# Lane_Detection_using_Sobel_Filter_Schema.net
KiCad netlist of a schematic drawn in Altium Designer
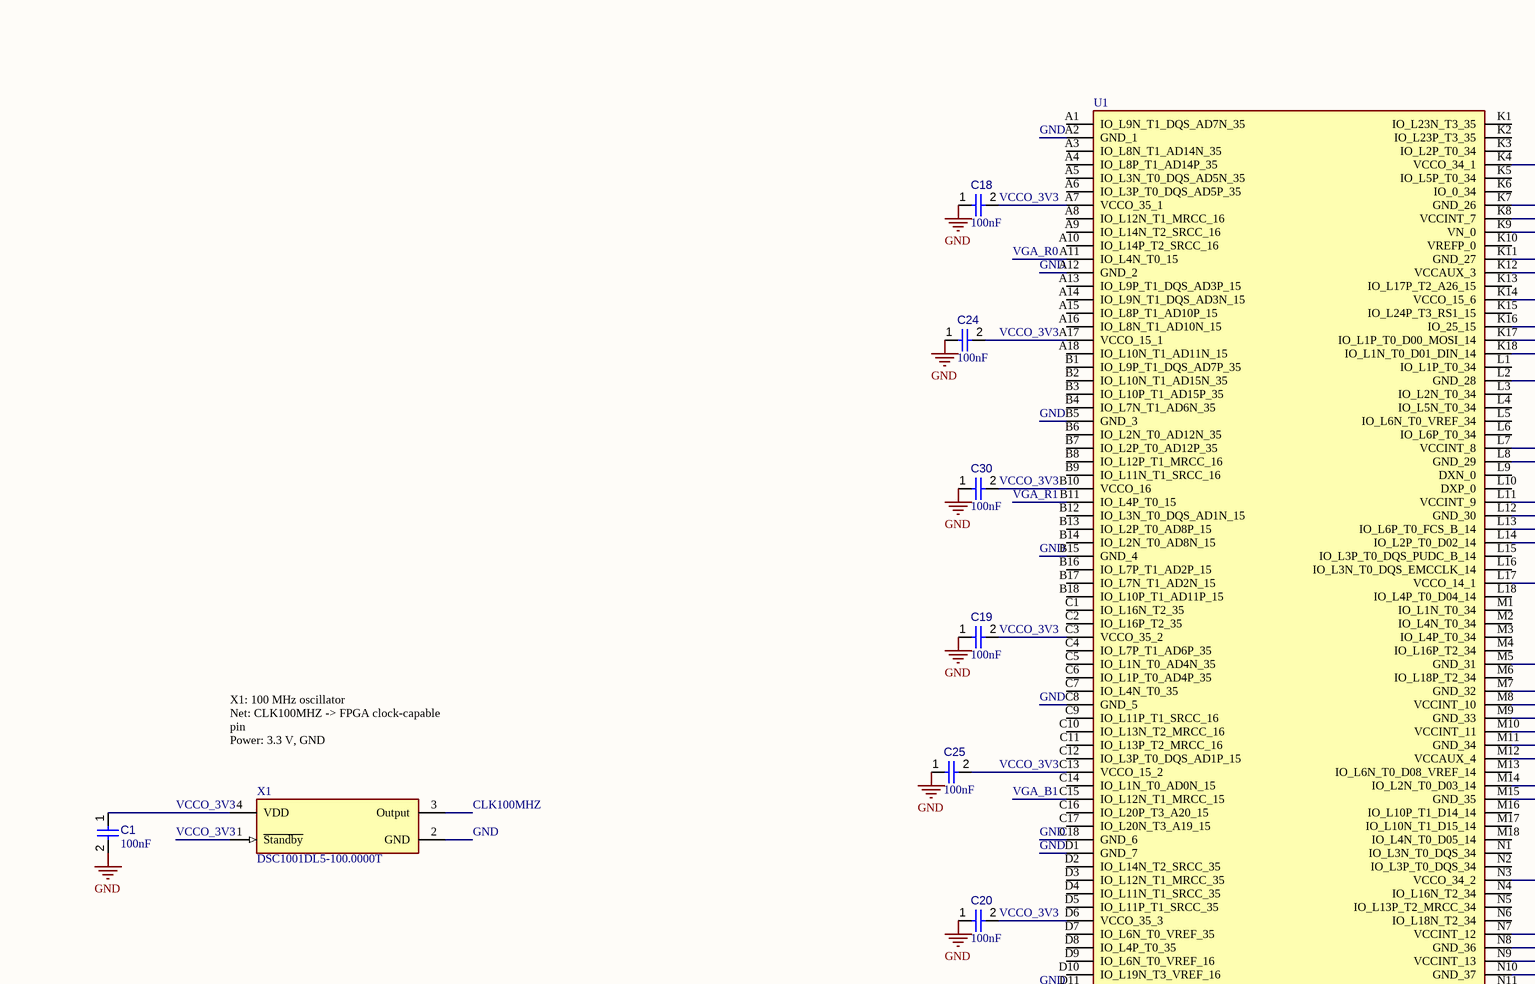
[diagram p0: Lane_Detection_using_Sobel_Filter_Schematic.SchDoc, top left]
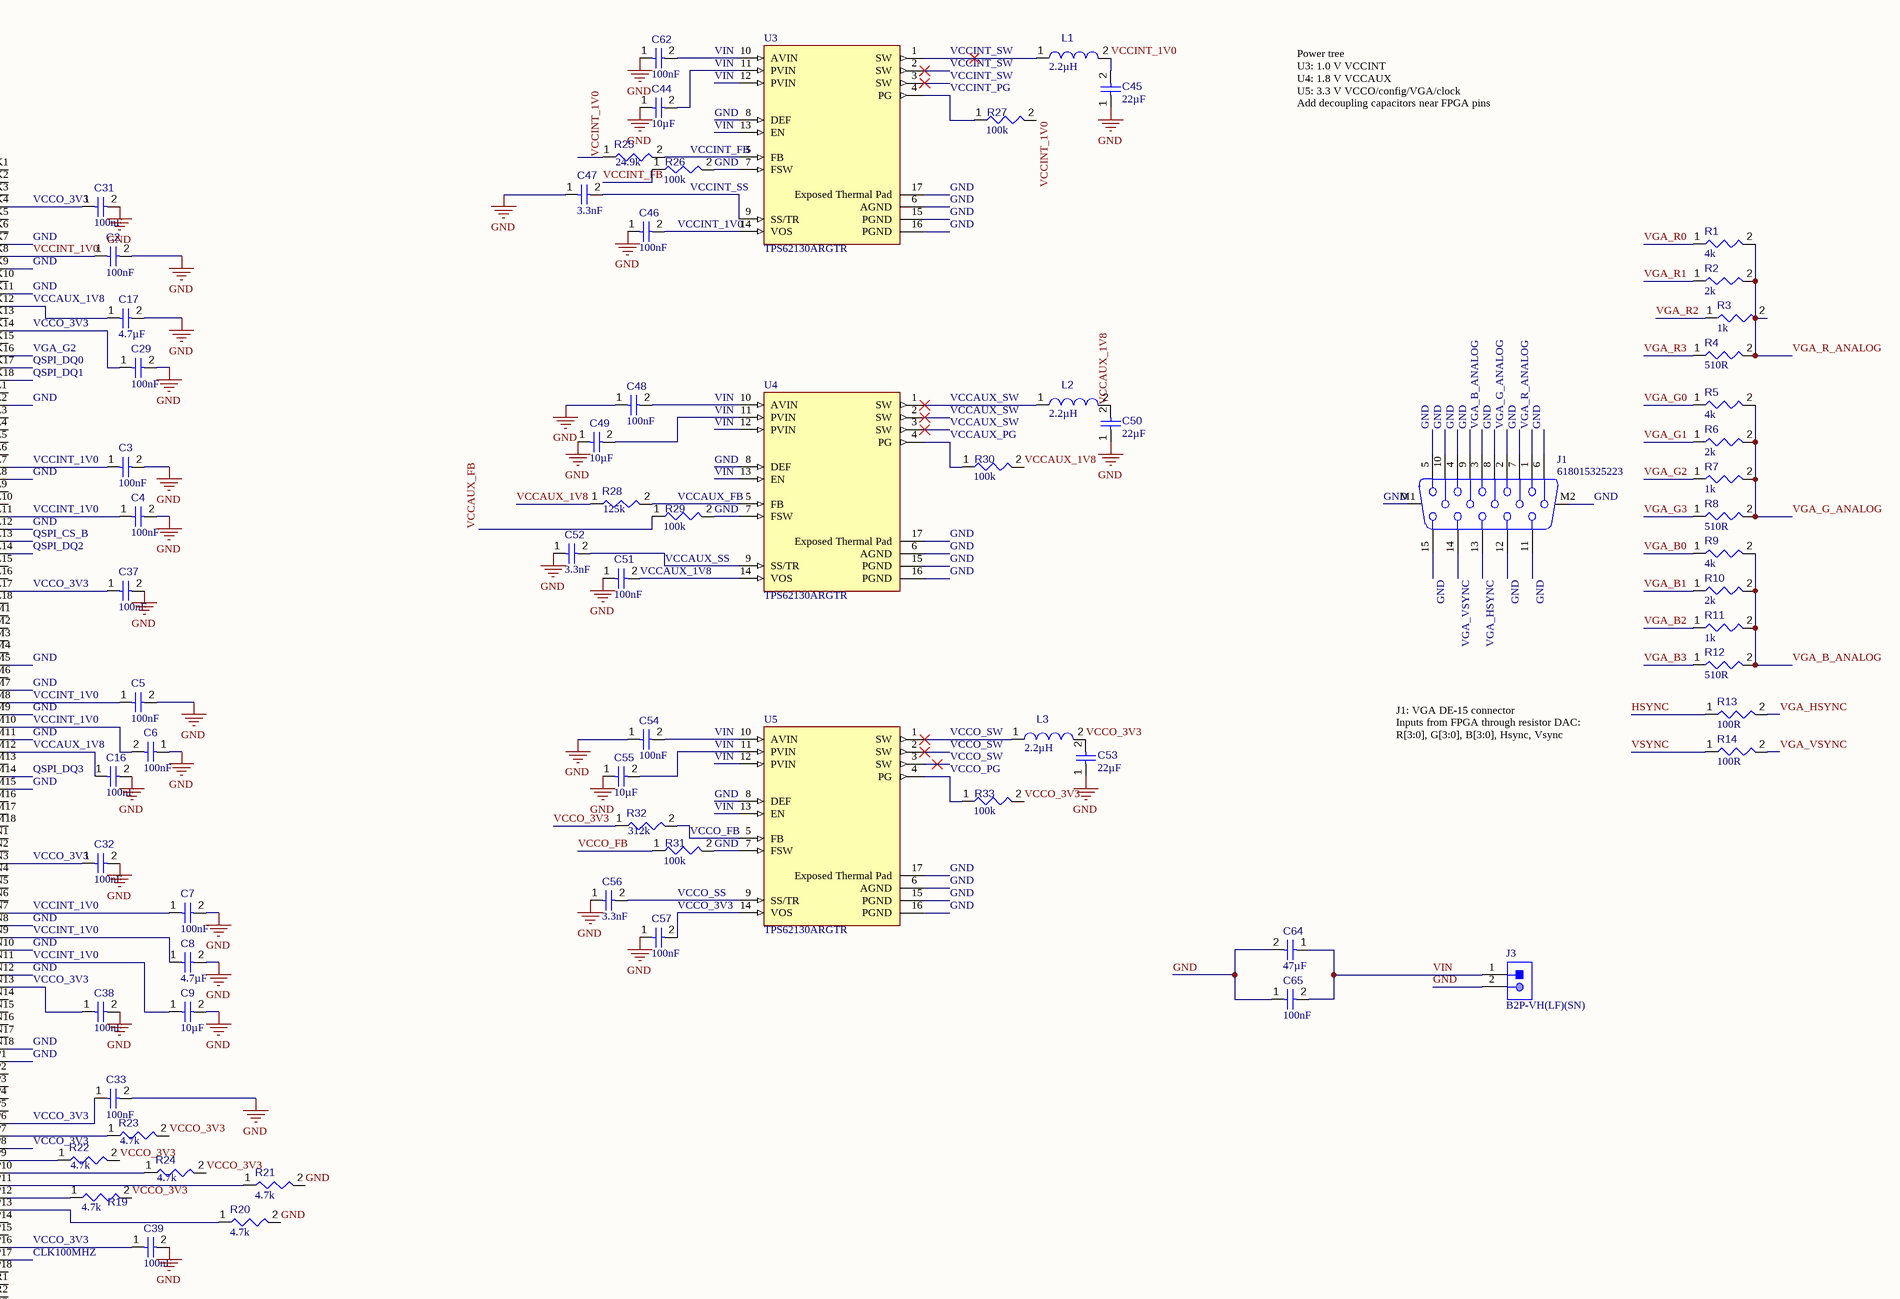
[diagram p1: Lane_Detection_using_Sobel_Filter_Schematic.SchDoc, top right]
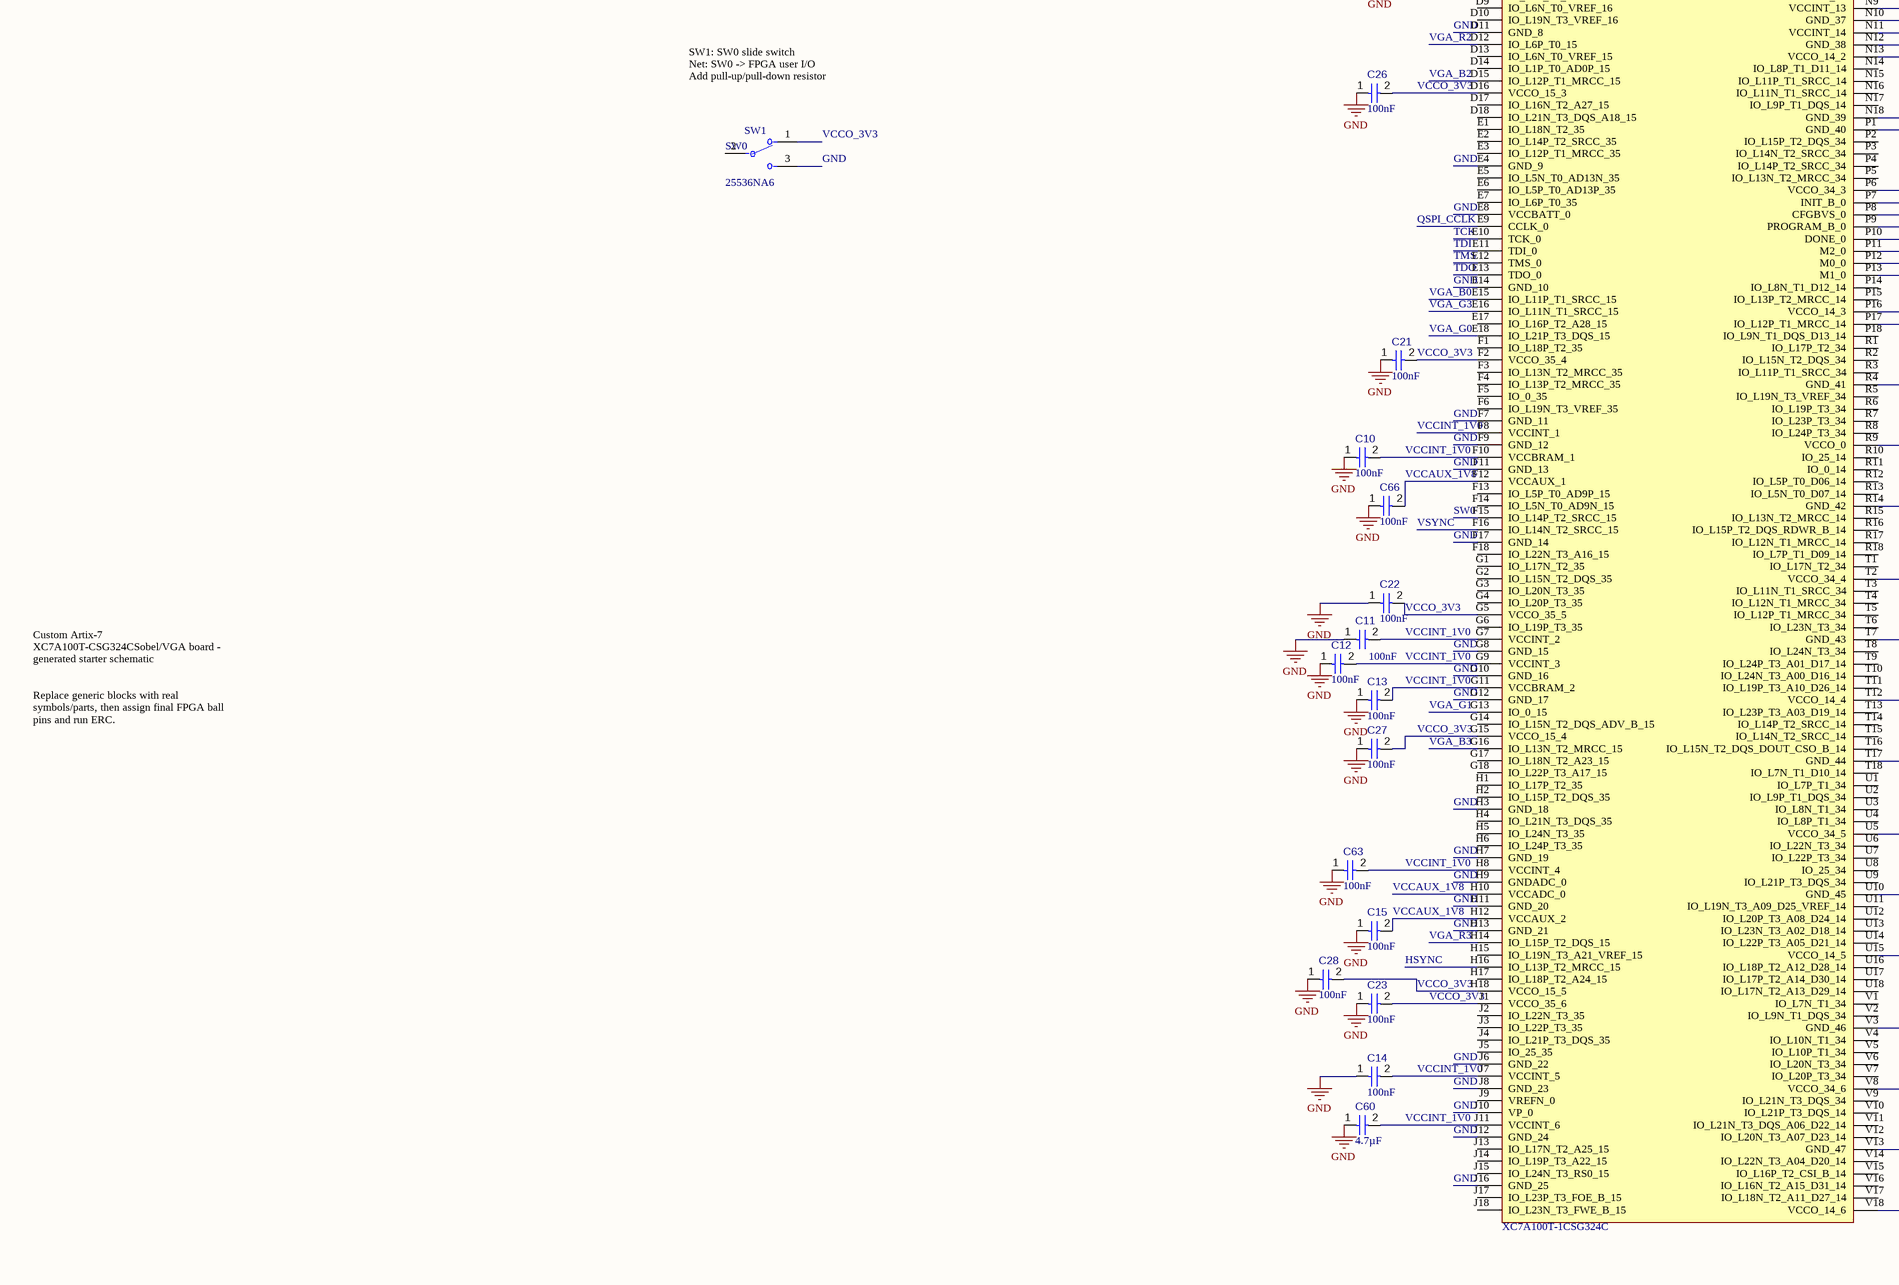
[diagram p2: Lane_Detection_using_Sobel_Filter_Schematic.SchDoc, bottom left]
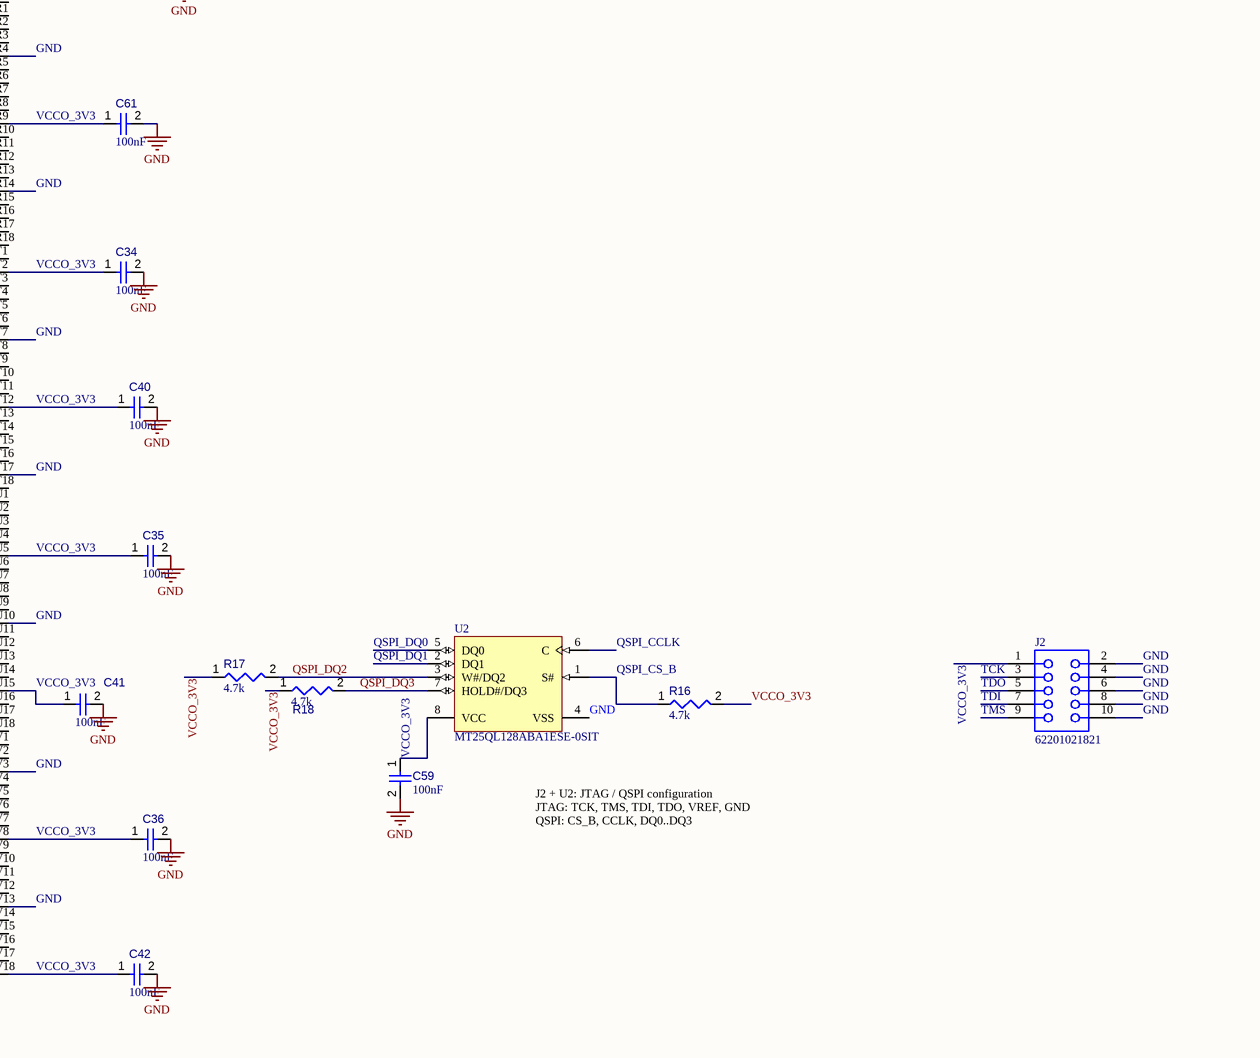
[diagram p3: Lane_Detection_using_Sobel_Filter_Schematic.SchDoc, bottom right]

(export (version "E")
  (design (tool "Eeschema 10.0.6"))
  (components
    (comp (ref "C1")
      (value "100nF")
      (footprint "CAPC1005X56X25NL10T15")
      (description "Chip Capacitor, 6.8 nF, +/- 10%, 16 V, 0402 (1005 Metric)")
      (fields (field (name "TOLERANCE") "10%") (field (name "Comment") "Capacitor 6.8 nF +/- 10% 16 V 0402"))
      (libsource (lib "Turja Barua") (part "CAP-NP-2"))
    )
    (comp (ref "C2")
      (value "100nF")
      (footprint "CAPC1005X56X25NL10T15")
      (description "Chip Capacitor, 6.8 nF, +/- 10%, 16 V, 0402 (1005 Metric)")
      (fields (field (name "TOLERANCE") "10%") (field (name "Comment") "Capacitor 6.8 nF +/- 10% 16 V 0402"))
      (libsource (lib "Turja Barua") (part "CAP-NP-2"))
    )
    (comp (ref "C3")
      (value "100nF")
      (footprint "CAPC1005X56X25NL10T15")
      (description "Chip Capacitor, 6.8 nF, +/- 10%, 16 V, 0402 (1005 Metric)")
      (fields (field (name "TOLERANCE") "10%") (field (name "Comment") "Capacitor 6.8 nF +/- 10% 16 V 0402"))
      (libsource (lib "Turja Barua") (part "CAP-NP-2"))
    )
    (comp (ref "C4")
      (value "100nF")
      (footprint "CAPC1005X56X25NL10T15")
      (description "Chip Capacitor, 6.8 nF, +/- 10%, 16 V, 0402 (1005 Metric)")
      (fields (field (name "TOLERANCE") "10%") (field (name "Comment") "Capacitor 6.8 nF +/- 10% 16 V 0402"))
      (libsource (lib "Turja Barua") (part "CAP-NP-2"))
    )
    (comp (ref "C5")
      (value "100nF")
      (footprint "CAPC1005X56X25NL10T15")
      (description "Chip Capacitor, 6.8 nF, +/- 10%, 16 V, 0402 (1005 Metric)")
      (fields (field (name "TOLERANCE") "10%") (field (name "Comment") "Capacitor 6.8 nF +/- 10% 16 V 0402"))
      (libsource (lib "Turja Barua") (part "CAP-NP-2"))
    )
    (comp (ref "C6")
      (value "100nF")
      (footprint "CAPC1005X56X25NL10T15")
      (description "Chip Capacitor, 6.8 nF, +/- 10%, 16 V, 0402 (1005 Metric)")
      (fields (field (name "TOLERANCE") "10%") (field (name "Comment") "Capacitor 6.8 nF +/- 10% 16 V 0402"))
      (libsource (lib "Turja Barua") (part "CAP-NP-2"))
    )
    (comp (ref "C7")
      (value "100nF")
      (footprint "CAPC1005X56X25NL10T15")
      (description "Chip Capacitor, 6.8 nF, +/- 10%, 16 V, 0402 (1005 Metric)")
      (fields (field (name "TOLERANCE") "10%") (field (name "Comment") "Capacitor 6.8 nF +/- 10% 16 V 0402"))
      (libsource (lib "Turja Barua") (part "CAP-NP-2"))
    )
    (comp (ref "C8")
      (value "4.7µF")
      (footprint "CAPC3216X180X50NL20T25")
      (description "Chip Capacitor, 10 uF, +/- 10%, 16 V, 1206 (3216 Metric)")
      (fields (field (name "TOLERANCE") "10%") (field (name "Comment") "Capacitor 10 uF +/- 10% 16 V 1206"))
      (libsource (lib "Turja Barua") (part "CAP-NP-2"))
    )
    (comp (ref "C9")
      (value "10µF")
      (footprint "CAPC3216X180X50NL20T25")
      (description "Chip Capacitor, 10 uF, +/- 10%, 16 V, 1206 (3216 Metric)")
      (fields (field (name "TOLERANCE") "10%") (field (name "Comment") "Capacitor 10 uF +/- 10% 16 V 1206"))
      (libsource (lib "Turja Barua") (part "CAP-NP-2"))
    )
    (comp (ref "C10")
      (value "100nF")
      (footprint "CAPC1005X56X25NL10T15")
      (description "Chip Capacitor, 6.8 nF, +/- 10%, 16 V, 0402 (1005 Metric)")
      (fields (field (name "TOLERANCE") "10%") (field (name "Comment") "Capacitor 6.8 nF +/- 10% 16 V 0402"))
      (libsource (lib "Turja Barua") (part "CAP-NP-2"))
    )
    (comp (ref "C11")
      (value "100nF")
      (footprint "CAPC1005X56X25NL10T15")
      (description "Chip Capacitor, 6.8 nF, +/- 10%, 16 V, 0402 (1005 Metric)")
      (fields (field (name "TOLERANCE") "10%") (field (name "Comment") "Capacitor 6.8 nF +/- 10% 16 V 0402"))
      (libsource (lib "Turja Barua") (part "CAP-NP-2"))
    )
    (comp (ref "C12")
      (value "100nF")
      (footprint "CAPC1005X56X25NL10T15")
      (description "Chip Capacitor, 6.8 nF, +/- 10%, 16 V, 0402 (1005 Metric)")
      (fields (field (name "TOLERANCE") "10%") (field (name "Comment") "Capacitor 6.8 nF +/- 10% 16 V 0402"))
      (libsource (lib "Turja Barua") (part "CAP-NP-2"))
    )
    (comp (ref "C13")
      (value "100nF")
      (footprint "CAPC1005X56X25NL10T15")
      (description "Chip Capacitor, 6.8 nF, +/- 10%, 16 V, 0402 (1005 Metric)")
      (fields (field (name "TOLERANCE") "10%") (field (name "Comment") "Capacitor 6.8 nF +/- 10% 16 V 0402"))
      (libsource (lib "Turja Barua") (part "CAP-NP-2"))
    )
    (comp (ref "C14")
      (value "100nF")
      (footprint "CAPC1005X56X25NL10T15")
      (description "Chip Capacitor, 6.8 nF, +/- 10%, 16 V, 0402 (1005 Metric)")
      (fields (field (name "TOLERANCE") "10%") (field (name "Comment") "Capacitor 6.8 nF +/- 10% 16 V 0402"))
      (libsource (lib "Turja Barua") (part "CAP-NP-2"))
    )
    (comp (ref "C15")
      (value "100nF")
      (footprint "CAPC1005X56X25NL10T15")
      (description "Chip Capacitor, 6.8 nF, +/- 10%, 16 V, 0402 (1005 Metric)")
      (fields (field (name "TOLERANCE") "10%") (field (name "Comment") "Capacitor 6.8 nF +/- 10% 16 V 0402"))
      (libsource (lib "Turja Barua") (part "CAP-NP-2"))
    )
    (comp (ref "C16")
      (value "100nF")
      (footprint "CAPC1005X56X25NL10T15")
      (description "Chip Capacitor, 6.8 nF, +/- 10%, 16 V, 0402 (1005 Metric)")
      (fields (field (name "TOLERANCE") "10%") (field (name "Comment") "Capacitor 6.8 nF +/- 10% 16 V 0402"))
      (libsource (lib "Turja Barua") (part "CAP-NP-2"))
    )
    (comp (ref "C17")
      (value "4.7µF")
      (footprint "CAPC3216X180X50NL20T25")
      (description "Chip Capacitor, 10 uF, +/- 10%, 16 V, 1206 (3216 Metric)")
      (fields (field (name "TOLERANCE") "10%") (field (name "Comment") "Capacitor 10 uF +/- 10% 16 V 1206"))
      (libsource (lib "Turja Barua") (part "CAP-NP-2"))
    )
    (comp (ref "C18")
      (value "100nF")
      (footprint "CAPC1005X56X25NL10T15")
      (description "Chip Capacitor, 6.8 nF, +/- 10%, 16 V, 0402 (1005 Metric)")
      (fields (field (name "TOLERANCE") "10%") (field (name "Comment") "Capacitor 6.8 nF +/- 10% 16 V 0402"))
      (libsource (lib "Turja Barua") (part "CAP-NP-2"))
    )
    (comp (ref "C19")
      (value "100nF")
      (footprint "CAPC1005X56X25NL10T15")
      (description "Chip Capacitor, 6.8 nF, +/- 10%, 16 V, 0402 (1005 Metric)")
      (fields (field (name "TOLERANCE") "10%") (field (name "Comment") "Capacitor 6.8 nF +/- 10% 16 V 0402"))
      (libsource (lib "Turja Barua") (part "CAP-NP-2"))
    )
    (comp (ref "C20")
      (value "100nF")
      (footprint "CAPC1005X56X25NL10T15")
      (description "Chip Capacitor, 6.8 nF, +/- 10%, 16 V, 0402 (1005 Metric)")
      (fields (field (name "TOLERANCE") "10%") (field (name "Comment") "Capacitor 6.8 nF +/- 10% 16 V 0402"))
      (libsource (lib "Turja Barua") (part "CAP-NP-2"))
    )
    (comp (ref "C21")
      (value "100nF")
      (footprint "CAPC1005X56X25NL10T15")
      (description "Chip Capacitor, 6.8 nF, +/- 10%, 16 V, 0402 (1005 Metric)")
      (fields (field (name "TOLERANCE") "10%") (field (name "Comment") "Capacitor 6.8 nF +/- 10% 16 V 0402"))
      (libsource (lib "Turja Barua") (part "CAP-NP-2"))
    )
    (comp (ref "C22")
      (value "100nF")
      (footprint "CAPC1005X56X25NL10T15")
      (description "Chip Capacitor, 6.8 nF, +/- 10%, 16 V, 0402 (1005 Metric)")
      (fields (field (name "TOLERANCE") "10%") (field (name "Comment") "Capacitor 6.8 nF +/- 10% 16 V 0402"))
      (libsource (lib "Turja Barua") (part "CAP-NP-2"))
    )
    (comp (ref "C23")
      (value "100nF")
      (footprint "CAPC1005X56X25NL10T15")
      (description "Chip Capacitor, 6.8 nF, +/- 10%, 16 V, 0402 (1005 Metric)")
      (fields (field (name "TOLERANCE") "10%") (field (name "Comment") "Capacitor 6.8 nF +/- 10% 16 V 0402"))
      (libsource (lib "Turja Barua") (part "CAP-NP-2"))
    )
    (comp (ref "C24")
      (value "100nF")
      (footprint "CAPC1005X56X25NL10T15")
      (description "Chip Capacitor, 6.8 nF, +/- 10%, 16 V, 0402 (1005 Metric)")
      (fields (field (name "TOLERANCE") "10%") (field (name "Comment") "Capacitor 6.8 nF +/- 10% 16 V 0402"))
      (libsource (lib "Turja Barua") (part "CAP-NP-2"))
    )
    (comp (ref "C25")
      (value "100nF")
      (footprint "CAPC1005X56X25NL10T15")
      (description "Chip Capacitor, 6.8 nF, +/- 10%, 16 V, 0402 (1005 Metric)")
      (fields (field (name "TOLERANCE") "10%") (field (name "Comment") "Capacitor 6.8 nF +/- 10% 16 V 0402"))
      (libsource (lib "Turja Barua") (part "CAP-NP-2"))
    )
    (comp (ref "C26")
      (value "100nF")
      (footprint "CAPC1005X56X25NL10T15")
      (description "Chip Capacitor, 6.8 nF, +/- 10%, 16 V, 0402 (1005 Metric)")
      (fields (field (name "TOLERANCE") "10%") (field (name "Comment") "Capacitor 6.8 nF +/- 10% 16 V 0402"))
      (libsource (lib "Turja Barua") (part "CAP-NP-2"))
    )
    (comp (ref "C27")
      (value "100nF")
      (footprint "CAPC1005X56X25NL10T15")
      (description "Chip Capacitor, 6.8 nF, +/- 10%, 16 V, 0402 (1005 Metric)")
      (fields (field (name "TOLERANCE") "10%") (field (name "Comment") "Capacitor 6.8 nF +/- 10% 16 V 0402"))
      (libsource (lib "Turja Barua") (part "CAP-NP-2"))
    )
    (comp (ref "C28")
      (value "100nF")
      (footprint "CAPC1005X56X25NL10T15")
      (description "Chip Capacitor, 6.8 nF, +/- 10%, 16 V, 0402 (1005 Metric)")
      (fields (field (name "TOLERANCE") "10%") (field (name "Comment") "Capacitor 6.8 nF +/- 10% 16 V 0402"))
      (libsource (lib "Turja Barua") (part "CAP-NP-2"))
    )
    (comp (ref "C29")
      (value "100nF")
      (footprint "CAPC1005X56X25NL10T15")
      (description "Chip Capacitor, 6.8 nF, +/- 10%, 16 V, 0402 (1005 Metric)")
      (fields (field (name "TOLERANCE") "10%") (field (name "Comment") "Capacitor 6.8 nF +/- 10% 16 V 0402"))
      (libsource (lib "Turja Barua") (part "CAP-NP-2"))
    )
    (comp (ref "C30")
      (value "100nF")
      (footprint "CAPC1005X56X25NL10T15")
      (description "Chip Capacitor, 6.8 nF, +/- 10%, 16 V, 0402 (1005 Metric)")
      (fields (field (name "TOLERANCE") "10%") (field (name "Comment") "Capacitor 6.8 nF +/- 10% 16 V 0402"))
      (libsource (lib "Turja Barua") (part "CAP-NP-2"))
    )
    (comp (ref "C31")
      (value "100nF")
      (footprint "CAPC1005X56X25NL10T15")
      (description "Chip Capacitor, 6.8 nF, +/- 10%, 16 V, 0402 (1005 Metric)")
      (fields (field (name "TOLERANCE") "10%") (field (name "Comment") "Capacitor 6.8 nF +/- 10% 16 V 0402"))
      (libsource (lib "Turja Barua") (part "CAP-NP-2"))
    )
    (comp (ref "C32")
      (value "100nF")
      (footprint "CAPC1005X56X25NL10T15")
      (description "Chip Capacitor, 6.8 nF, +/- 10%, 16 V, 0402 (1005 Metric)")
      (fields (field (name "TOLERANCE") "10%") (field (name "Comment") "Capacitor 6.8 nF +/- 10% 16 V 0402"))
      (libsource (lib "Turja Barua") (part "CAP-NP-2"))
    )
    (comp (ref "C33")
      (value "100nF")
      (footprint "CAPC1005X56X25NL10T15")
      (description "Chip Capacitor, 6.8 nF, +/- 10%, 16 V, 0402 (1005 Metric)")
      (fields (field (name "TOLERANCE") "10%") (field (name "Comment") "Capacitor 6.8 nF +/- 10% 16 V 0402"))
      (libsource (lib "Turja Barua") (part "CAP-NP-2"))
    )
    (comp (ref "C34")
      (value "100nF")
      (footprint "CAPC1005X56X25NL10T15")
      (description "Chip Capacitor, 6.8 nF, +/- 10%, 16 V, 0402 (1005 Metric)")
      (fields (field (name "TOLERANCE") "10%") (field (name "Comment") "Capacitor 6.8 nF +/- 10% 16 V 0402"))
      (libsource (lib "Turja Barua") (part "CAP-NP-2"))
    )
    (comp (ref "C35")
      (value "100nF")
      (footprint "CAPC1005X56X25NL10T15")
      (description "Chip Capacitor, 6.8 nF, +/- 10%, 16 V, 0402 (1005 Metric)")
      (fields (field (name "TOLERANCE") "10%") (field (name "Comment") "Capacitor 6.8 nF +/- 10% 16 V 0402"))
      (libsource (lib "Turja Barua") (part "CAP-NP-2"))
    )
    (comp (ref "C36")
      (value "100nF")
      (footprint "CAPC1005X56X25NL10T15")
      (description "Chip Capacitor, 6.8 nF, +/- 10%, 16 V, 0402 (1005 Metric)")
      (fields (field (name "TOLERANCE") "10%") (field (name "Comment") "Capacitor 6.8 nF +/- 10% 16 V 0402"))
      (libsource (lib "Turja Barua") (part "CAP-NP-2"))
    )
    (comp (ref "C37")
      (value "100nF")
      (footprint "CAPC1005X56X25NL10T15")
      (description "Chip Capacitor, 6.8 nF, +/- 10%, 16 V, 0402 (1005 Metric)")
      (fields (field (name "TOLERANCE") "10%") (field (name "Comment") "Capacitor 6.8 nF +/- 10% 16 V 0402"))
      (libsource (lib "Turja Barua") (part "CAP-NP-2"))
    )
    (comp (ref "C38")
      (value "100nF")
      (footprint "CAPC1005X56X25NL10T15")
      (description "Chip Capacitor, 6.8 nF, +/- 10%, 16 V, 0402 (1005 Metric)")
      (fields (field (name "TOLERANCE") "10%") (field (name "Comment") "Capacitor 6.8 nF +/- 10% 16 V 0402"))
      (libsource (lib "Turja Barua") (part "CAP-NP-2"))
    )
    (comp (ref "C39")
      (value "100nF")
      (footprint "CAPC1005X56X25NL10T15")
      (description "Chip Capacitor, 6.8 nF, +/- 10%, 16 V, 0402 (1005 Metric)")
      (fields (field (name "TOLERANCE") "10%") (field (name "Comment") "Capacitor 6.8 nF +/- 10% 16 V 0402"))
      (libsource (lib "Turja Barua") (part "CAP-NP-2"))
    )
    (comp (ref "C40")
      (value "100nF")
      (footprint "CAPC1005X56X25NL10T15")
      (description "Chip Capacitor, 6.8 nF, +/- 10%, 16 V, 0402 (1005 Metric)")
      (fields (field (name "TOLERANCE") "10%") (field (name "Comment") "Capacitor 6.8 nF +/- 10% 16 V 0402"))
      (libsource (lib "Turja Barua") (part "CAP-NP-2"))
    )
    (comp (ref "C41")
      (value "100nF")
      (footprint "CAPC1005X56X25NL10T15")
      (description "Chip Capacitor, 6.8 nF, +/- 10%, 16 V, 0402 (1005 Metric)")
      (fields (field (name "TOLERANCE") "10%") (field (name "Comment") "Capacitor 6.8 nF +/- 10% 16 V 0402"))
      (libsource (lib "Turja Barua") (part "CAP-NP-2"))
    )
    (comp (ref "C42")
      (value "100nF")
      (footprint "CAPC1005X56X25NL10T15")
      (description "Chip Capacitor, 6.8 nF, +/- 10%, 16 V, 0402 (1005 Metric)")
      (fields (field (name "TOLERANCE") "10%") (field (name "Comment") "Capacitor 6.8 nF +/- 10% 16 V 0402"))
      (libsource (lib "Turja Barua") (part "CAP-NP-2"))
    )
    (comp (ref "C44")
      (value "10µF")
      (footprint "CAPC3216X180X50NL20T25")
      (description "Chip Capacitor, 10 uF, +/- 10%, 16 V, 1206 (3216 Metric)")
      (fields (field (name "TOLERANCE") "10%") (field (name "Comment") "Capacitor 10 uF +/- 10% 16 V 1206"))
      (libsource (lib "Turja Barua") (part "CAP-NP-2"))
    )
    (comp (ref "C45")
      (value "22µF")
      (footprint "CAPC3216X180X50NL20T25")
      (description "Chip Capacitor, 10 uF, +/- 10%, 16 V, 1206 (3216 Metric)")
      (fields (field (name "TOLERANCE") "10%") (field (name "Comment") "Capacitor 10 uF +/- 10% 16 V 1206"))
      (libsource (lib "Turja Barua") (part "CAP-NP-2"))
    )
    (comp (ref "C46")
      (value "100nF")
      (footprint "CAPC1005X56X25NL10T15")
      (description "Chip Capacitor, 6.8 nF, +/- 10%, 16 V, 0402 (1005 Metric)")
      (fields (field (name "TOLERANCE") "10%") (field (name "Comment") "Capacitor 6.8 nF +/- 10% 16 V 0402"))
      (libsource (lib "Turja Barua") (part "CAP-NP-2"))
    )
    (comp (ref "C47")
      (value "3.3nF")
      (footprint "CAPC1005X56X25NL10T15")
      (description "Chip Capacitor, 6.8 nF, +/- 10%, 16 V, 0402 (1005 Metric)")
      (fields (field (name "TOLERANCE") "10%") (field (name "Comment") "Capacitor 6.8 nF +/- 10% 16 V 0402"))
      (libsource (lib "Turja Barua") (part "CAP-NP-2"))
    )
    (comp (ref "C48")
      (value "100nF")
      (footprint "CAPC1005X56X25NL10T15")
      (description "Chip Capacitor, 6.8 nF, +/- 10%, 16 V, 0402 (1005 Metric)")
      (fields (field (name "TOLERANCE") "10%") (field (name "Comment") "Capacitor 6.8 nF +/- 10% 16 V 0402"))
      (libsource (lib "Turja Barua") (part "CAP-NP-2"))
    )
    (comp (ref "C49")
      (value "10µF")
      (footprint "CAPC3216X180X50NL20T25")
      (description "Chip Capacitor, 10 uF, +/- 10%, 16 V, 1206 (3216 Metric)")
      (fields (field (name "TOLERANCE") "10%") (field (name "Comment") "Capacitor 10 uF +/- 10% 16 V 1206"))
      (libsource (lib "Turja Barua") (part "CAP-NP-2"))
    )
    (comp (ref "C50")
      (value "22µF")
      (footprint "CAPC3216X180X50NL20T25")
      (description "Chip Capacitor, 10 uF, +/- 10%, 16 V, 1206 (3216 Metric)")
      (fields (field (name "TOLERANCE") "10%") (field (name "Comment") "Capacitor 10 uF +/- 10% 16 V 1206"))
      (libsource (lib "Turja Barua") (part "CAP-NP-2"))
    )
    (comp (ref "C51")
      (value "100nF")
      (footprint "CAPC1005X56X25NL10T15")
      (description "Chip Capacitor, 6.8 nF, +/- 10%, 16 V, 0402 (1005 Metric)")
      (fields (field (name "TOLERANCE") "10%") (field (name "Comment") "Capacitor 6.8 nF +/- 10% 16 V 0402"))
      (libsource (lib "Turja Barua") (part "CAP-NP-2"))
    )
    (comp (ref "C52")
      (value "3.3nF")
      (footprint "CAPC1005X56X25NL10T15")
      (description "Chip Capacitor, 6.8 nF, +/- 10%, 16 V, 0402 (1005 Metric)")
      (fields (field (name "TOLERANCE") "10%") (field (name "Comment") "Capacitor 6.8 nF +/- 10% 16 V 0402"))
      (libsource (lib "Turja Barua") (part "CAP-NP-2"))
    )
    (comp (ref "C53")
      (value "22µF")
      (footprint "CAPC3216X180X50NL20T25")
      (description "Chip Capacitor, 10 uF, +/- 10%, 16 V, 1206 (3216 Metric)")
      (fields (field (name "TOLERANCE") "10%") (field (name "Comment") "Capacitor 10 uF +/- 10% 16 V 1206"))
      (libsource (lib "Turja Barua") (part "CAP-NP-2"))
    )
    (comp (ref "C54")
      (value "100nF")
      (footprint "CAPC1005X56X25NL10T15")
      (description "Chip Capacitor, 6.8 nF, +/- 10%, 16 V, 0402 (1005 Metric)")
      (fields (field (name "TOLERANCE") "10%") (field (name "Comment") "Capacitor 6.8 nF +/- 10% 16 V 0402"))
      (libsource (lib "Turja Barua") (part "CAP-NP-2"))
    )
    (comp (ref "C55")
      (value "10µF")
      (footprint "CAPC3216X180X50NL20T25")
      (description "Chip Capacitor, 10 uF, +/- 10%, 16 V, 1206 (3216 Metric)")
      (fields (field (name "TOLERANCE") "10%") (field (name "Comment") "Capacitor 10 uF +/- 10% 16 V 1206"))
      (libsource (lib "Turja Barua") (part "CAP-NP-2"))
    )
    (comp (ref "C56")
      (value "3.3nF")
      (footprint "CAPC1005X56X25NL10T15")
      (description "Chip Capacitor, 6.8 nF, +/- 10%, 16 V, 0402 (1005 Metric)")
      (fields (field (name "TOLERANCE") "10%") (field (name "Comment") "Capacitor 6.8 nF +/- 10% 16 V 0402"))
      (libsource (lib "Turja Barua") (part "CAP-NP-2"))
    )
    (comp (ref "C57")
      (value "100nF")
      (footprint "CAPC1005X56X25NL10T15")
      (description "Chip Capacitor, 6.8 nF, +/- 10%, 16 V, 0402 (1005 Metric)")
      (fields (field (name "TOLERANCE") "10%") (field (name "Comment") "Capacitor 6.8 nF +/- 10% 16 V 0402"))
      (libsource (lib "Turja Barua") (part "CAP-NP-2"))
    )
    (comp (ref "C59")
      (value "100nF")
      (footprint "CAPC1005X56X25NL10T15")
      (description "Chip Capacitor, 6.8 nF, +/- 10%, 16 V, 0402 (1005 Metric)")
      (fields (field (name "TOLERANCE") "10%") (field (name "Comment") "Capacitor 6.8 nF +/- 10% 16 V 0402"))
      (libsource (lib "Turja Barua") (part "CAP-NP-2"))
    )
    (comp (ref "C60")
      (value "4.7µF")
      (footprint "CAPC3216X180X50NL20T25")
      (description "Chip Capacitor, 10 uF, +/- 10%, 16 V, 1206 (3216 Metric)")
      (fields (field (name "TOLERANCE") "10%") (field (name "Comment") "Capacitor 10 uF +/- 10% 16 V 1206"))
      (libsource (lib "Turja Barua") (part "CAP-NP-2"))
    )
    (comp (ref "C61")
      (value "100nF")
      (footprint "CAPC1005X56X25NL10T15")
      (description "Chip Capacitor, 6.8 nF, +/- 10%, 16 V, 0402 (1005 Metric)")
      (fields (field (name "TOLERANCE") "10%") (field (name "Comment") "Capacitor 6.8 nF +/- 10% 16 V 0402"))
      (libsource (lib "Turja Barua") (part "CAP-NP-2"))
    )
    (comp (ref "C62")
      (value "100nF")
      (footprint "CAPC1005X56X25NL10T15")
      (description "Chip Capacitor, 6.8 nF, +/- 10%, 16 V, 0402 (1005 Metric)")
      (fields (field (name "TOLERANCE") "10%") (field (name "Comment") "Capacitor 6.8 nF +/- 10% 16 V 0402"))
      (libsource (lib "Turja Barua") (part "CAP-NP-2"))
    )
    (comp (ref "C63")
      (value "100nF")
      (footprint "CAPC1005X56X25NL10T15")
      (description "Chip Capacitor, 6.8 nF, +/- 10%, 16 V, 0402 (1005 Metric)")
      (fields (field (name "TOLERANCE") "10%") (field (name "Comment") "Capacitor 6.8 nF +/- 10% 16 V 0402"))
      (libsource (lib "Turja Barua") (part "CAP-NP-2"))
    )
    (comp (ref "C64")
      (value "47µF")
      (footprint "CAPC3216X180X50NL20T25")
      (description "Chip Capacitor, 10 uF, +/- 10%, 16 V, 1206 (3216 Metric)")
      (fields (field (name "TOLERANCE") "10%") (field (name "Comment") "Capacitor 10 uF +/- 10% 16 V 1206"))
      (libsource (lib "Turja Barua") (part "CAP-NP-2"))
    )
    (comp (ref "C65")
      (value "100nF")
      (footprint "CAPC1005X56X25NL10T15")
      (description "Chip Capacitor, 6.8 nF, +/- 10%, 16 V, 0402 (1005 Metric)")
      (fields (field (name "TOLERANCE") "10%") (field (name "Comment") "Capacitor 6.8 nF +/- 10% 16 V 0402"))
      (libsource (lib "Turja Barua") (part "CAP-NP-2"))
    )
    (comp (ref "C66")
      (value "100nF")
      (footprint "CAPC1005X56X25NL10T15")
      (description "Chip Capacitor, 6.8 nF, +/- 10%, 16 V, 0402 (1005 Metric)")
      (fields (field (name "TOLERANCE") "10%") (field (name "Comment") "Capacitor 6.8 nF +/- 10% 16 V 0402"))
      (libsource (lib "Turja Barua") (part "CAP-NP-2"))
    )
    (comp (ref "J1")
      (value "618015325223")
      (footprint "618015325223")
      (description "D-sub, Female High Density Angled Pcb Connector Without Hex Screw, 15 Pins")
      (libsource (lib "Md Mostafizur Rahman") (part "D-Sub_Female_15p_High Density"))
    )
    (comp (ref "J2")
      (value "62201021821")
      (footprint "62201021821")
      (description "Connector Header Surface Mount 10 position 0.050\" (1.27mm)-JTAG Connector")
      (libsource (lib "Md Mostafizur Rahman") (part "Header_Female_2R_10P"))
    )
    (comp (ref "J3")
      (value "B2P-VH(LF)(SN)")
      (footprint "JST-B2P-VH(LF)(SN)_V")
      (fields (field (name "MANUFACTURER") "JST"))
      (libsource (lib "Turja Barua") (part "CN-1P-M-R2"))
    )
    (comp (ref "L1")
      (value "2.2µH")
      (footprint "SUSUMU-PCMB063T_V")
      (description "Shielded Wirewound Inductor, 2.2 uH, +/- 20%, -20 to 120 degC, 2-Pin SMD, RoHS, Tape and Reel")
      (fields (field (name "TOLERANCE") "20%") (field (name "Comment") "PCMB063T-2R2MS"))
      (libsource (lib "Turja Barua") (part "CMP-001-0020-1"))
    )
    (comp (ref "L2")
      (value "2.2µH")
      (footprint "SUSUMU-PCMB063T_V")
      (description "Shielded Wirewound Inductor, 2.2 uH, +/- 20%, -20 to 120 degC, 2-Pin SMD, RoHS, Tape and Reel")
      (fields (field (name "TOLERANCE") "20%") (field (name "Comment") "PCMB063T-2R2MS"))
      (libsource (lib "Turja Barua") (part "CMP-001-0020-1"))
    )
    (comp (ref "L3")
      (value "2.2µH")
      (footprint "SUSUMU-PCMB063T_V")
      (description "Shielded Wirewound Inductor, 2.2 uH, +/- 20%, -20 to 120 degC, 2-Pin SMD, RoHS, Tape and Reel")
      (fields (field (name "TOLERANCE") "20%") (field (name "Comment") "PCMB063T-2R2MS"))
      (libsource (lib "Turja Barua") (part "CMP-001-0020-1"))
    )
    (comp (ref "R1")
      (value "4k")
      (footprint "RESA60-630X240")
      (description "Axial Resistor, 475 Ohm, +/- 1%, 0.25 W, -55 to 155 degC, 2-Pin THD, RoHS, Bulk")
      (fields (field (name "MANUFACTURER") "Yageo") (field (name "TOLERANCE") "1%"))
      (libsource (lib "Turja Barua") (part "RES-2"))
    )
    (comp (ref "R2")
      (value "2k")
      (footprint "RESA60-630X240")
      (description "Axial Resistor, 475 Ohm, +/- 1%, 0.25 W, -55 to 155 degC, 2-Pin THD, RoHS, Bulk")
      (fields (field (name "MANUFACTURER") "Yageo") (field (name "TOLERANCE") "1%"))
      (libsource (lib "Turja Barua") (part "RES-2"))
    )
    (comp (ref "R3")
      (value "1k")
      (footprint "RESA60-630X240")
      (description "Axial Resistor, 475 Ohm, +/- 1%, 0.25 W, -55 to 155 degC, 2-Pin THD, RoHS, Bulk")
      (fields (field (name "MANUFACTURER") "Yageo") (field (name "TOLERANCE") "1%"))
      (libsource (lib "Turja Barua") (part "RES-2"))
    )
    (comp (ref "R4")
      (value "510R")
      (footprint "RESA60-630X240")
      (description "Axial Resistor, 475 Ohm, +/- 1%, 0.25 W, -55 to 155 degC, 2-Pin THD, RoHS, Bulk")
      (fields (field (name "MANUFACTURER") "Yageo") (field (name "TOLERANCE") "1%"))
      (libsource (lib "Turja Barua") (part "RES-2"))
    )
    (comp (ref "R5")
      (value "4k")
      (footprint "RESA60-630X240")
      (description "Axial Resistor, 475 Ohm, +/- 1%, 0.25 W, -55 to 155 degC, 2-Pin THD, RoHS, Bulk")
      (fields (field (name "MANUFACTURER") "Yageo") (field (name "TOLERANCE") "1%"))
      (libsource (lib "Turja Barua") (part "RES-2"))
    )
    (comp (ref "R6")
      (value "2k")
      (footprint "RESA60-630X240")
      (description "Axial Resistor, 475 Ohm, +/- 1%, 0.25 W, -55 to 155 degC, 2-Pin THD, RoHS, Bulk")
      (fields (field (name "MANUFACTURER") "Yageo") (field (name "TOLERANCE") "1%"))
      (libsource (lib "Turja Barua") (part "RES-2"))
    )
    (comp (ref "R7")
      (value "1k")
      (footprint "RESA60-630X240")
      (description "Axial Resistor, 475 Ohm, +/- 1%, 0.25 W, -55 to 155 degC, 2-Pin THD, RoHS, Bulk")
      (fields (field (name "MANUFACTURER") "Yageo") (field (name "TOLERANCE") "1%"))
      (libsource (lib "Turja Barua") (part "RES-2"))
    )
    (comp (ref "R8")
      (value "510R")
      (footprint "RESA60-630X240")
      (description "Axial Resistor, 475 Ohm, +/- 1%, 0.25 W, -55 to 155 degC, 2-Pin THD, RoHS, Bulk")
      (fields (field (name "MANUFACTURER") "Yageo") (field (name "TOLERANCE") "1%"))
      (libsource (lib "Turja Barua") (part "RES-2"))
    )
    (comp (ref "R9")
      (value "4k")
      (footprint "RESA60-630X240")
      (description "Axial Resistor, 475 Ohm, +/- 1%, 0.25 W, -55 to 155 degC, 2-Pin THD, RoHS, Bulk")
      (fields (field (name "MANUFACTURER") "Yageo") (field (name "TOLERANCE") "1%"))
      (libsource (lib "Turja Barua") (part "RES-2"))
    )
    (comp (ref "R10")
      (value "2k")
      (footprint "RESA60-630X240")
      (description "Axial Resistor, 475 Ohm, +/- 1%, 0.25 W, -55 to 155 degC, 2-Pin THD, RoHS, Bulk")
      (fields (field (name "MANUFACTURER") "Yageo") (field (name "TOLERANCE") "1%"))
      (libsource (lib "Turja Barua") (part "RES-2"))
    )
    (comp (ref "R11")
      (value "1k")
      (footprint "RESA60-630X240")
      (description "Axial Resistor, 475 Ohm, +/- 1%, 0.25 W, -55 to 155 degC, 2-Pin THD, RoHS, Bulk")
      (fields (field (name "MANUFACTURER") "Yageo") (field (name "TOLERANCE") "1%"))
      (libsource (lib "Turja Barua") (part "RES-2"))
    )
    (comp (ref "R12")
      (value "510R")
      (footprint "RESA60-630X240")
      (description "Axial Resistor, 475 Ohm, +/- 1%, 0.25 W, -55 to 155 degC, 2-Pin THD, RoHS, Bulk")
      (fields (field (name "MANUFACTURER") "Yageo") (field (name "TOLERANCE") "1%"))
      (libsource (lib "Turja Barua") (part "RES-2"))
    )
    (comp (ref "R13")
      (value "100R")
      (footprint "RESA60-630X240")
      (description "Axial Resistor, 475 Ohm, +/- 1%, 0.25 W, -55 to 155 degC, 2-Pin THD, RoHS, Bulk")
      (fields (field (name "MANUFACTURER") "Yageo") (field (name "TOLERANCE") "1%"))
      (libsource (lib "Turja Barua") (part "RES-2"))
    )
    (comp (ref "R14")
      (value "100R")
      (footprint "RESA60-630X240")
      (description "Axial Resistor, 475 Ohm, +/- 1%, 0.25 W, -55 to 155 degC, 2-Pin THD, RoHS, Bulk")
      (fields (field (name "MANUFACTURER") "Yageo") (field (name "TOLERANCE") "1%"))
      (libsource (lib "Turja Barua") (part "RES-2"))
    )
    (comp (ref "R16")
      (value "4.7k")
      (footprint "RESC0402(1005)_L")
      (description "84K5 0.063W 1% 0402 (1005 Metric)  SMD")
      (fields (field (name "POWER") "63mW") (field (name "TOLERANCE") "1%"))
      (libsource (lib "Turja Barua") (part "84D5KR2F"))
    )
    (comp (ref "R17")
      (value "4.7k")
      (footprint "RESC0402(1005)_L")
      (description "84K5 0.063W 1% 0402 (1005 Metric)  SMD")
      (fields (field (name "POWER") "63mW") (field (name "TOLERANCE") "1%"))
      (libsource (lib "Turja Barua") (part "84D5KR2F"))
    )
    (comp (ref "R18")
      (value "4.7k")
      (footprint "RESC0402(1005)_L")
      (description "84K5 0.063W 1% 0402 (1005 Metric)  SMD")
      (fields (field (name "POWER") "63mW") (field (name "TOLERANCE") "1%"))
      (libsource (lib "Turja Barua") (part "84D5KR2F"))
    )
    (comp (ref "R19")
      (value "4.7k")
      (footprint "RESC0402(1005)_L")
      (description "84K5 0.063W 1% 0402 (1005 Metric)  SMD")
      (fields (field (name "POWER") "63mW") (field (name "TOLERANCE") "1%"))
      (libsource (lib "Turja Barua") (part "84D5KR2F"))
    )
    (comp (ref "R20")
      (value "4.7k")
      (footprint "RESC0402(1005)_L")
      (description "84K5 0.063W 1% 0402 (1005 Metric)  SMD")
      (fields (field (name "POWER") "63mW") (field (name "TOLERANCE") "1%"))
      (libsource (lib "Turja Barua") (part "84D5KR2F"))
    )
    (comp (ref "R21")
      (value "4.7k")
      (footprint "RESC0402(1005)_L")
      (description "84K5 0.063W 1% 0402 (1005 Metric)  SMD")
      (fields (field (name "POWER") "63mW") (field (name "TOLERANCE") "1%"))
      (libsource (lib "Turja Barua") (part "84D5KR2F"))
    )
    (comp (ref "R22")
      (value "4.7k")
      (footprint "RESC0402(1005)_L")
      (description "84K5 0.063W 1% 0402 (1005 Metric)  SMD")
      (fields (field (name "POWER") "63mW") (field (name "TOLERANCE") "1%"))
      (libsource (lib "Turja Barua") (part "84D5KR2F"))
    )
    (comp (ref "R23")
      (value "4.7k")
      (footprint "RESC0402(1005)_L")
      (description "84K5 0.063W 1% 0402 (1005 Metric)  SMD")
      (fields (field (name "POWER") "63mW") (field (name "TOLERANCE") "1%"))
      (libsource (lib "Turja Barua") (part "84D5KR2F"))
    )
    (comp (ref "R24")
      (value "4.7k")
      (footprint "RESC0402(1005)_L")
      (description "84K5 0.063W 1% 0402 (1005 Metric)  SMD")
      (fields (field (name "POWER") "63mW") (field (name "TOLERANCE") "1%"))
      (libsource (lib "Turja Barua") (part "84D5KR2F"))
    )
    (comp (ref "R25")
      (value "24.9k")
      (footprint "RESC0402(1005)_L")
      (description "84K5 0.063W 1% 0402 (1005 Metric)  SMD")
      (fields (field (name "POWER") "63mW") (field (name "TOLERANCE") "1%"))
      (libsource (lib "Turja Barua") (part "84D5KR2F"))
    )
    (comp (ref "R26")
      (value "100k")
      (footprint "RESC0402(1005)_L")
      (description "84K5 0.063W 1% 0402 (1005 Metric)  SMD")
      (fields (field (name "POWER") "63mW") (field (name "TOLERANCE") "1%"))
      (libsource (lib "Turja Barua") (part "84D5KR2F"))
    )
    (comp (ref "R27")
      (value "100k")
      (footprint "RESC0402(1005)_L")
      (description "84K5 0.063W 1% 0402 (1005 Metric)  SMD")
      (fields (field (name "POWER") "63mW") (field (name "TOLERANCE") "1%"))
      (libsource (lib "Turja Barua") (part "84D5KR2F"))
    )
    (comp (ref "R28")
      (value "125k")
      (footprint "RESC0402(1005)_L")
      (description "84K5 0.063W 1% 0402 (1005 Metric)  SMD")
      (fields (field (name "POWER") "63mW") (field (name "TOLERANCE") "1%"))
      (libsource (lib "Turja Barua") (part "84D5KR2F"))
    )
    (comp (ref "R29")
      (value "100k")
      (footprint "RESC0402(1005)_L")
      (description "84K5 0.063W 1% 0402 (1005 Metric)  SMD")
      (fields (field (name "POWER") "63mW") (field (name "TOLERANCE") "1%"))
      (libsource (lib "Turja Barua") (part "84D5KR2F"))
    )
    (comp (ref "R30")
      (value "100k")
      (footprint "RESC0402(1005)_L")
      (description "84K5 0.063W 1% 0402 (1005 Metric)  SMD")
      (fields (field (name "POWER") "63mW") (field (name "TOLERANCE") "1%"))
      (libsource (lib "Turja Barua") (part "84D5KR2F"))
    )
    (comp (ref "R31")
      (value "100k")
      (footprint "RESC0402(1005)_L")
      (description "84K5 0.063W 1% 0402 (1005 Metric)  SMD")
      (fields (field (name "POWER") "63mW") (field (name "TOLERANCE") "1%"))
      (libsource (lib "Turja Barua") (part "84D5KR2F"))
    )
    (comp (ref "R32")
      (value "312k")
      (footprint "RESC0402(1005)_L")
      (description "84K5 0.063W 1% 0402 (1005 Metric)  SMD")
      (fields (field (name "POWER") "63mW") (field (name "TOLERANCE") "1%"))
      (libsource (lib "Turja Barua") (part "84D5KR2F"))
    )
    (comp (ref "R33")
      (value "100k")
      (footprint "RESC0402(1005)_L")
      (description "84K5 0.063W 1% 0402 (1005 Metric)  SMD")
      (fields (field (name "POWER") "63mW") (field (name "TOLERANCE") "1%"))
      (libsource (lib "Turja Barua") (part "84D5KR2F"))
    )
    (comp (ref "SW1")
      (value "25536NA6")
      (footprint "FP-25536NA6-0")
      (description "Switch Slide ON ON SPDT Side Slide 1A 30VDC 20000Cycles PC Pins Thru-Hole")
      (libsource (lib "Md Mostafizur Rahman") (part "52c419afdc2a387c7d548259a9aeefb"))
    )
    (comp (ref "U1")
      (value "XC7A100T-1CSG324C")
      (footprint "BGA324C80P18X18_1500X1500X150")
      (description "IC FPGA ARTIX7 210 I/O 324CSBGA")
      (fields (field (name "MOUSER PART NUMBER") "217-C7A100T-1CSG324C"))
      (libsource (lib "XC7A100T-1CSG324C") (part "XC7A100T-1CSG324C"))
    )
    (comp (ref "U2")
      (value "MT25QL128ABA1ESE-0SIT")
      (footprint "MICT-SE-8_M")
      (description "3.6 V 35 mA 128 Mbit 133 MHz Surface Mount FLASH - NOR Memory IC - SOIC-16")
      (libsource (lib "Md Mostafizur Rahman") (part "MICT-MT25QL128ABA-SOP2-8"))
    )
    (comp (ref "U3")
      (value "TPS62130ARGTR")
      (footprint "FP-RGT0016C-IPC_C")
      (description "3-V to 17-V, 3-A step-down converter with DCS-control in 3x3 QFN package 16-VQFN -40 to 125")
      (libsource (lib "Md Mostafizur Rahman") (part "dca50ec3578d8d47edbd046ea96d7ac"))
    )
    (comp (ref "U4")
      (value "TPS62130ARGTR")
      (footprint "FP-RGT0016C-IPC_C")
      (description "3-V to 17-V, 3-A step-down converter with DCS-control in 3x3 QFN package 16-VQFN -40 to 125")
      (libsource (lib "Md Mostafizur Rahman") (part "dca50ec3578d8d47edbd046ea96d7ac"))
    )
    (comp (ref "U5")
      (value "TPS62130ARGTR")
      (footprint "FP-RGT0016C-IPC_C")
      (description "3-V to 17-V, 3-A step-down converter with DCS-control in 3x3 QFN package 16-VQFN -40 to 125")
      (libsource (lib "Md Mostafizur Rahman") (part "dca50ec3578d8d47edbd046ea96d7ac"))
    )
    (comp (ref "X1")
      (value "DSC1001DL5-100.0000T")
      (footprint "FP-CDFN2520-4LD-PL-1-MFG")
      (description "3.3 V 100 MHz Surface Mount Low-Power Precision CMOS Oscillator - VDFN-4")
      (libsource (lib "Md Mostafizur Rahman") (part "679220c3c234322ca52724a1007024e"))
    )
  )
  (nets
    (net (code "1") (name "/CLK100MHZ") (class "Default")
      (node (ref "U1") (pin "P17") (pinfunction "IO_L12P_T1_MRCC_14_P17") (pintype "passive"))
      (node (ref "X1") (pin "3") (pinfunction "Output_3") (pintype "passive"))
    )
    (net (code "2") (name "/HSYNC") (class "Default")
      (node (ref "R13") (pin "1") (pinfunction "1_1") (pintype "passive"))
      (node (ref "U1") (pin "H16") (pinfunction "IO_L13P_T2_MRCC_15_H16") (pintype "passive"))
    )
    (net (code "3") (name "/QSPI_CCLK") (class "Default")
      (node (ref "U1") (pin "E9") (pinfunction "CCLK_0_E9") (pintype "passive"))
      (node (ref "U2") (pin "6") (pinfunction "C_6") (pintype "input"))
    )
    (net (code "4") (name "/QSPI_CS_B") (class "Default")
      (node (ref "R16") (pin "1") (pinfunction "1_1") (pintype "passive"))
      (node (ref "U1") (pin "L13") (pinfunction "IO_L6P_T0_FCS_B_14_L13") (pintype "passive"))
      (node (ref "U2") (pin "1") (pinfunction "S#_1") (pintype "input"))
    )
    (net (code "5") (name "/QSPI_DQ0") (class "Default")
      (node (ref "U1") (pin "K17") (pinfunction "IO_L1P_T0_D00_MOSI_14_K17") (pintype "passive"))
      (node (ref "U2") (pin "5") (pinfunction "DQ0_5") (pintype "bidirectional"))
    )
    (net (code "6") (name "/QSPI_DQ1") (class "Default")
      (node (ref "U1") (pin "K18") (pinfunction "IO_L1N_T0_D01_DIN_14_K18") (pintype "passive"))
      (node (ref "U2") (pin "2") (pinfunction "DQ1_2") (pintype "bidirectional"))
    )
    (net (code "7") (name "/QSPI_DQ2") (class "Default")
      (node (ref "R17") (pin "2") (pinfunction "2_2") (pintype "passive"))
      (node (ref "U1") (pin "L14") (pinfunction "IO_L2P_T0_D02_14_L14") (pintype "passive"))
      (node (ref "U2") (pin "3") (pinfunction "W#/DQ2_3") (pintype "bidirectional"))
    )
    (net (code "8") (name "/QSPI_DQ3") (class "Default")
      (node (ref "R18") (pin "2") (pinfunction "2_2") (pintype "passive"))
      (node (ref "U1") (pin "M14") (pinfunction "IO_L2N_T0_D03_14_M14") (pintype "passive"))
      (node (ref "U2") (pin "7") (pinfunction "HOLD#/DQ3_7") (pintype "bidirectional"))
    )
    (net (code "9") (name "/SW0") (class "Default")
      (node (ref "SW1") (pin "2") (pinfunction "2_2") (pintype "passive"))
      (node (ref "U1") (pin "F15") (pinfunction "IO_L14P_T2_SRCC_15_F15") (pintype "passive"))
    )
    (net (code "10") (name "/TCK") (class "Default")
      (node (ref "J2") (pin "3") (pinfunction "3_3") (pintype "passive"))
      (node (ref "U1") (pin "E10") (pinfunction "TCK_0_E10") (pintype "passive"))
    )
    (net (code "11") (name "/TDI") (class "Default")
      (node (ref "J2") (pin "7") (pinfunction "7_7") (pintype "passive"))
      (node (ref "U1") (pin "E11") (pinfunction "TDI_0_E11") (pintype "passive"))
    )
    (net (code "12") (name "/TDO") (class "Default")
      (node (ref "J2") (pin "5") (pinfunction "5_5") (pintype "passive"))
      (node (ref "U1") (pin "E13") (pinfunction "TDO_0_E13") (pintype "passive"))
    )
    (net (code "13") (name "/TMS") (class "Default")
      (node (ref "J2") (pin "9") (pinfunction "9_9") (pintype "passive"))
      (node (ref "U1") (pin "E12") (pinfunction "TMS_0_E12") (pintype "passive"))
    )
    (net (code "14") (name "/VCCAUX_1V8") (class "Default")
      (node (ref "C15") (pin "2") (pinfunction "2_2") (pintype "passive"))
      (node (ref "C16") (pin "1") (pinfunction "1_1") (pintype "passive"))
      (node (ref "C17") (pin "1") (pinfunction "1_1") (pintype "passive"))
      (node (ref "C50") (pin "2") (pinfunction "2_2") (pintype "passive"))
      (node (ref "C51") (pin "2") (pinfunction "2_2") (pintype "passive"))
      (node (ref "C66") (pin "2") (pinfunction "2_2") (pintype "passive"))
      (node (ref "L2") (pin "2") (pinfunction "2_2") (pintype "passive"))
      (node (ref "R28") (pin "1") (pinfunction "1_1") (pintype "passive"))
      (node (ref "R30") (pin "2") (pinfunction "2_2") (pintype "passive"))
      (node (ref "U1") (pin "F12") (pinfunction "VCCAUX_1_F12") (pintype "passive"))
      (node (ref "U1") (pin "H10") (pinfunction "VCCADC_0_H10") (pintype "passive"))
      (node (ref "U1") (pin "H12") (pinfunction "VCCAUX_2_H12") (pintype "passive"))
      (node (ref "U1") (pin "K12") (pinfunction "VCCAUX_3_K12") (pintype "passive"))
      (node (ref "U1") (pin "M12") (pinfunction "VCCAUX_4_M12") (pintype "passive"))
      (node (ref "U4") (pin "14") (pinfunction "VOS_14") (pintype "input"))
    )
    (net (code "15") (name "/VCCAUX_FB") (class "Default")
      (node (ref "R28") (pin "2") (pinfunction "2_2") (pintype "passive"))
      (node (ref "R29") (pin "1") (pinfunction "1_1") (pintype "passive"))
      (node (ref "U4") (pin "5") (pinfunction "FB_5") (pintype "input"))
    )
    (net (code "16") (name "/VCCAUX_PG") (class "Default")
      (node (ref "R30") (pin "1") (pinfunction "1_1") (pintype "passive"))
      (node (ref "U4") (pin "4") (pinfunction "PG_4") (pintype "output"))
    )
    (net (code "17") (name "/VCCAUX_SS") (class "Default")
      (node (ref "C52") (pin "2") (pinfunction "2_2") (pintype "passive"))
      (node (ref "U4") (pin "9") (pinfunction "SS/TR_9") (pintype "input"))
    )
    (net (code "18") (name "/VCCAUX_SW") (class "Default")
      (node (ref "L2") (pin "1") (pinfunction "1_1") (pintype "passive"))
      (node (ref "U4") (pin "1") (pinfunction "SW_1") (pintype "output"))
      (node (ref "U4") (pin "2") (pinfunction "SW_2") (pintype "output"))
      (node (ref "U4") (pin "3") (pinfunction "SW_3") (pintype "output"))
    )
    (net (code "19") (name "/VCCINT_1V0") (class "Default")
      (node (ref "C10") (pin "2") (pinfunction "2_2") (pintype "passive"))
      (node (ref "C11") (pin "2") (pinfunction "2_2") (pintype "passive"))
      (node (ref "C12") (pin "2") (pinfunction "2_2") (pintype "passive"))
      (node (ref "C13") (pin "2") (pinfunction "2_2") (pintype "passive"))
      (node (ref "C14") (pin "2") (pinfunction "2_2") (pintype "passive"))
      (node (ref "C2") (pin "1") (pinfunction "1_1") (pintype "passive"))
      (node (ref "C3") (pin "1") (pinfunction "1_1") (pintype "passive"))
      (node (ref "C4") (pin "1") (pinfunction "1_1") (pintype "passive"))
      (node (ref "C45") (pin "2") (pinfunction "2_2") (pintype "passive"))
      (node (ref "C46") (pin "2") (pinfunction "2_2") (pintype "passive"))
      (node (ref "C5") (pin "1") (pinfunction "1_1") (pintype "passive"))
      (node (ref "C6") (pin "2") (pinfunction "2_2") (pintype "passive"))
      (node (ref "C60") (pin "2") (pinfunction "2_2") (pintype "passive"))
      (node (ref "C63") (pin "2") (pinfunction "2_2") (pintype "passive"))
      (node (ref "C7") (pin "1") (pinfunction "1_1") (pintype "passive"))
      (node (ref "C8") (pin "1") (pinfunction "1_1") (pintype "passive"))
      (node (ref "C9") (pin "1") (pinfunction "1_1") (pintype "passive"))
      (node (ref "L1") (pin "2") (pinfunction "2_2") (pintype "passive"))
      (node (ref "R25") (pin "1") (pinfunction "1_1") (pintype "passive"))
      (node (ref "R27") (pin "2") (pinfunction "2_2") (pintype "passive"))
      (node (ref "U1") (pin "F10") (pinfunction "VCCBRAM_1_F10") (pintype "passive"))
      (node (ref "U1") (pin "F8") (pinfunction "VCCINT_1_F8") (pintype "passive"))
      (node (ref "U1") (pin "G11") (pinfunction "VCCBRAM_2_G11") (pintype "passive"))
      (node (ref "U1") (pin "G7") (pinfunction "VCCINT_2_G7") (pintype "passive"))
      (node (ref "U1") (pin "G9") (pinfunction "VCCINT_3_G9") (pintype "passive"))
      (node (ref "U1") (pin "H8") (pinfunction "VCCINT_4_H8") (pintype "passive"))
      (node (ref "U1") (pin "J11") (pinfunction "VCCINT_6_J11") (pintype "passive"))
      (node (ref "U1") (pin "J7") (pinfunction "VCCINT_5_J7") (pintype "passive"))
      (node (ref "U1") (pin "K8") (pinfunction "VCCINT_7_K8") (pintype "passive"))
      (node (ref "U1") (pin "L11") (pinfunction "VCCINT_9_L11") (pintype "passive"))
      (node (ref "U1") (pin "L7") (pinfunction "VCCINT_8_L7") (pintype "passive"))
      (node (ref "U1") (pin "M10") (pinfunction "VCCINT_11_M10") (pintype "passive"))
      (node (ref "U1") (pin "M8") (pinfunction "VCCINT_10_M8") (pintype "passive"))
      (node (ref "U1") (pin "N11") (pinfunction "VCCINT_14_N11") (pintype "passive"))
      (node (ref "U1") (pin "N7") (pinfunction "VCCINT_12_N7") (pintype "passive"))
      (node (ref "U1") (pin "N9") (pinfunction "VCCINT_13_N9") (pintype "passive"))
      (node (ref "U3") (pin "14") (pinfunction "VOS_14") (pintype "input"))
    )
    (net (code "20") (name "/VCCINT_FB") (class "Default")
      (node (ref "R25") (pin "2") (pinfunction "2_2") (pintype "passive"))
      (node (ref "R26") (pin "1") (pinfunction "1_1") (pintype "passive"))
      (node (ref "U3") (pin "5") (pinfunction "FB_5") (pintype "input"))
    )
    (net (code "21") (name "/VCCINT_PG") (class "Default")
      (node (ref "R27") (pin "1") (pinfunction "1_1") (pintype "passive"))
      (node (ref "U3") (pin "4") (pinfunction "PG_4") (pintype "output"))
    )
    (net (code "22") (name "/VCCINT_SS") (class "Default")
      (node (ref "C47") (pin "2") (pinfunction "2_2") (pintype "passive"))
      (node (ref "U3") (pin "9") (pinfunction "SS/TR_9") (pintype "input"))
    )
    (net (code "23") (name "/VCCINT_SW") (class "Default")
      (node (ref "L1") (pin "1") (pinfunction "1_1") (pintype "passive"))
      (node (ref "U3") (pin "1") (pinfunction "SW_1") (pintype "output"))
      (node (ref "U3") (pin "2") (pinfunction "SW_2") (pintype "output"))
      (node (ref "U3") (pin "3") (pinfunction "SW_3") (pintype "output"))
    )
    (net (code "24") (name "/VCCO_3V3") (class "Default")
      (node (ref "C1") (pin "1") (pinfunction "1_1") (pintype "passive"))
      (node (ref "C18") (pin "2") (pinfunction "2_2") (pintype "passive"))
      (node (ref "C19") (pin "2") (pinfunction "2_2") (pintype "passive"))
      (node (ref "C20") (pin "2") (pinfunction "2_2") (pintype "passive"))
      (node (ref "C21") (pin "2") (pinfunction "2_2") (pintype "passive"))
      (node (ref "C22") (pin "2") (pinfunction "2_2") (pintype "passive"))
      (node (ref "C23") (pin "2") (pinfunction "2_2") (pintype "passive"))
      (node (ref "C24") (pin "2") (pinfunction "2_2") (pintype "passive"))
      (node (ref "C25") (pin "2") (pinfunction "2_2") (pintype "passive"))
      (node (ref "C26") (pin "2") (pinfunction "2_2") (pintype "passive"))
      (node (ref "C27") (pin "2") (pinfunction "2_2") (pintype "passive"))
      (node (ref "C28") (pin "2") (pinfunction "2_2") (pintype "passive"))
      (node (ref "C29") (pin "1") (pinfunction "1_1") (pintype "passive"))
      (node (ref "C30") (pin "2") (pinfunction "2_2") (pintype "passive"))
      (node (ref "C31") (pin "1") (pinfunction "1_1") (pintype "passive"))
      (node (ref "C32") (pin "1") (pinfunction "1_1") (pintype "passive"))
      (node (ref "C33") (pin "1") (pinfunction "1_1") (pintype "passive"))
      (node (ref "C34") (pin "1") (pinfunction "1_1") (pintype "passive"))
      (node (ref "C35") (pin "1") (pinfunction "1_1") (pintype "passive"))
      (node (ref "C36") (pin "1") (pinfunction "1_1") (pintype "passive"))
      (node (ref "C37") (pin "1") (pinfunction "1_1") (pintype "passive"))
      (node (ref "C38") (pin "1") (pinfunction "1_1") (pintype "passive"))
      (node (ref "C39") (pin "1") (pinfunction "1_1") (pintype "passive"))
      (node (ref "C40") (pin "1") (pinfunction "1_1") (pintype "passive"))
      (node (ref "C41") (pin "1") (pinfunction "1_1") (pintype "passive"))
      (node (ref "C42") (pin "1") (pinfunction "1_1") (pintype "passive"))
      (node (ref "C53") (pin "2") (pinfunction "2_2") (pintype "passive"))
      (node (ref "C57") (pin "2") (pinfunction "2_2") (pintype "passive"))
      (node (ref "C59") (pin "1") (pinfunction "1_1") (pintype "passive"))
      (node (ref "C61") (pin "1") (pinfunction "1_1") (pintype "passive"))
      (node (ref "J2") (pin "1") (pinfunction "1_1") (pintype "passive"))
      (node (ref "L3") (pin "2") (pinfunction "2_2") (pintype "passive"))
      (node (ref "R16") (pin "2") (pinfunction "2_2") (pintype "passive"))
      (node (ref "R17") (pin "1") (pinfunction "1_1") (pintype "passive"))
      (node (ref "R18") (pin "1") (pinfunction "1_1") (pintype "passive"))
      (node (ref "R19") (pin "2") (pinfunction "2_2") (pintype "passive"))
      (node (ref "R22") (pin "2") (pinfunction "2_2") (pintype "passive"))
      (node (ref "R23") (pin "2") (pinfunction "2_2") (pintype "passive"))
      (node (ref "R24") (pin "2") (pinfunction "2_2") (pintype "passive"))
      (node (ref "R32") (pin "1") (pinfunction "1_1") (pintype "passive"))
      (node (ref "R33") (pin "2") (pinfunction "2_2") (pintype "passive"))
      (node (ref "SW1") (pin "1") (pinfunction "1_1") (pintype "passive"))
      (node (ref "U1") (pin "A17") (pinfunction "VCCO_15_1_A17") (pintype "passive"))
      (node (ref "U1") (pin "A7") (pinfunction "VCCO_35_1_A7") (pintype "passive"))
      (node (ref "U1") (pin "B10") (pinfunction "VCCO_16_B10") (pintype "passive"))
      (node (ref "U1") (pin "C13") (pinfunction "VCCO_15_2_C13") (pintype "passive"))
      (node (ref "U1") (pin "C3") (pinfunction "VCCO_35_2_C3") (pintype "passive"))
      (node (ref "U1") (pin "D16") (pinfunction "VCCO_15_3_D16") (pintype "passive"))
      (node (ref "U1") (pin "D6") (pinfunction "VCCO_35_3_D6") (pintype "passive"))
      (node (ref "U1") (pin "F2") (pinfunction "VCCO_35_4_F2") (pintype "passive"))
      (node (ref "U1") (pin "G15") (pinfunction "VCCO_15_4_G15") (pintype "passive"))
      (node (ref "U1") (pin "G5") (pinfunction "VCCO_35_5_G5") (pintype "passive"))
      (node (ref "U1") (pin "H18") (pinfunction "VCCO_15_5_H18") (pintype "passive"))
      (node (ref "U1") (pin "J1") (pinfunction "VCCO_35_6_J1") (pintype "passive"))
      (node (ref "U1") (pin "K14") (pinfunction "VCCO_15_6_K14") (pintype "passive"))
      (node (ref "U1") (pin "K4") (pinfunction "VCCO_34_1_K4") (pintype "passive"))
      (node (ref "U1") (pin "L17") (pinfunction "VCCO_14_1_L17") (pintype "passive"))
      (node (ref "U1") (pin "N13") (pinfunction "VCCO_14_2_N13") (pintype "passive"))
      (node (ref "U1") (pin "N3") (pinfunction "VCCO_34_2_N3") (pintype "passive"))
      (node (ref "U1") (pin "P16") (pinfunction "VCCO_14_3_P16") (pintype "passive"))
      (node (ref "U1") (pin "P6") (pinfunction "VCCO_34_3_P6") (pintype "passive"))
      (node (ref "U1") (pin "P8") (pinfunction "CFGBVS_0_P8") (pintype "passive"))
      (node (ref "U1") (pin "R9") (pinfunction "VCCO_0_R9") (pintype "passive"))
      (node (ref "U1") (pin "T12") (pinfunction "VCCO_14_4_T12") (pintype "passive"))
      (node (ref "U1") (pin "T2") (pinfunction "VCCO_34_4_T2") (pintype "passive"))
      (node (ref "U1") (pin "U15") (pinfunction "VCCO_14_5_U15") (pintype "passive"))
      (node (ref "U1") (pin "U5") (pinfunction "VCCO_34_5_U5") (pintype "passive"))
      (node (ref "U1") (pin "V18") (pinfunction "VCCO_14_6_V18") (pintype "passive"))
      (node (ref "U1") (pin "V8") (pinfunction "VCCO_34_6_V8") (pintype "passive"))
      (node (ref "U2") (pin "8") (pinfunction "VCC_8") (pintype "power_in"))
      (node (ref "U5") (pin "14") (pinfunction "VOS_14") (pintype "input"))
      (node (ref "X1") (pin "1") (pinfunction "~{Standby}_1") (pintype "input"))
      (node (ref "X1") (pin "4") (pinfunction "VDD_4") (pintype "power_in"))
    )
    (net (code "25") (name "/VCCO_FB") (class "Default")
      (node (ref "R31") (pin "1") (pinfunction "1_1") (pintype "passive"))
      (node (ref "R32") (pin "2") (pinfunction "2_2") (pintype "passive"))
      (node (ref "U5") (pin "5") (pinfunction "FB_5") (pintype "input"))
    )
    (net (code "26") (name "/VCCO_PG") (class "Default")
      (node (ref "R33") (pin "1") (pinfunction "1_1") (pintype "passive"))
      (node (ref "U5") (pin "4") (pinfunction "PG_4") (pintype "output"))
    )
    (net (code "27") (name "/VCCO_SS") (class "Default")
      (node (ref "C56") (pin "2") (pinfunction "2_2") (pintype "passive"))
      (node (ref "U5") (pin "9") (pinfunction "SS/TR_9") (pintype "input"))
    )
    (net (code "28") (name "/VCCO_SW") (class "Default")
      (node (ref "L3") (pin "1") (pinfunction "1_1") (pintype "passive"))
      (node (ref "U5") (pin "1") (pinfunction "SW_1") (pintype "output"))
      (node (ref "U5") (pin "2") (pinfunction "SW_2") (pintype "output"))
      (node (ref "U5") (pin "3") (pinfunction "SW_3") (pintype "output"))
    )
    (net (code "29") (name "/VGA_B0") (class "Default")
      (node (ref "R9") (pin "1") (pinfunction "1_1") (pintype "passive"))
      (node (ref "U1") (pin "E15") (pinfunction "IO_L11P_T1_SRCC_15_E15") (pintype "passive"))
    )
    (net (code "30") (name "/VGA_B1") (class "Default")
      (node (ref "R10") (pin "1") (pinfunction "1_1") (pintype "passive"))
      (node (ref "U1") (pin "C15") (pinfunction "IO_L12N_T1_MRCC_15_C15") (pintype "passive"))
    )
    (net (code "31") (name "/VGA_B2") (class "Default")
      (node (ref "R11") (pin "1") (pinfunction "1_1") (pintype "passive"))
      (node (ref "U1") (pin "D15") (pinfunction "IO_L12P_T1_MRCC_15_D15") (pintype "passive"))
    )
    (net (code "32") (name "/VGA_B3") (class "Default")
      (node (ref "R12") (pin "1") (pinfunction "1_1") (pintype "passive"))
      (node (ref "U1") (pin "G16") (pinfunction "IO_L13N_T2_MRCC_15_G16") (pintype "passive"))
    )
    (net (code "33") (name "/VGA_B_ANALOG") (class "Default")
      (node (ref "J1") (pin "3") (pinfunction "3_3") (pintype "passive"))
      (node (ref "R10") (pin "2") (pinfunction "2_2") (pintype "passive"))
      (node (ref "R11") (pin "2") (pinfunction "2_2") (pintype "passive"))
      (node (ref "R12") (pin "2") (pinfunction "2_2") (pintype "passive"))
      (node (ref "R9") (pin "2") (pinfunction "2_2") (pintype "passive"))
    )
    (net (code "34") (name "/VGA_G0") (class "Default")
      (node (ref "R5") (pin "1") (pinfunction "1_1") (pintype "passive"))
      (node (ref "U1") (pin "E18") (pinfunction "IO_L21P_T3_DQS_15_E18") (pintype "passive"))
    )
    (net (code "35") (name "/VGA_G1") (class "Default")
      (node (ref "R6") (pin "1") (pinfunction "1_1") (pintype "passive"))
      (node (ref "U1") (pin "G13") (pinfunction "IO_0_15_G13") (pintype "passive"))
    )
    (net (code "36") (name "/VGA_G2") (class "Default")
      (node (ref "R7") (pin "1") (pinfunction "1_1") (pintype "passive"))
      (node (ref "U1") (pin "K16") (pinfunction "IO_25_15_K16") (pintype "passive"))
    )
    (net (code "37") (name "/VGA_G3") (class "Default")
      (node (ref "R8") (pin "1") (pinfunction "1_1") (pintype "passive"))
      (node (ref "U1") (pin "E16") (pinfunction "IO_L11N_T1_SRCC_15_E16") (pintype "passive"))
    )
    (net (code "38") (name "/VGA_G_ANALOG") (class "Default")
      (node (ref "J1") (pin "2") (pinfunction "2_2") (pintype "passive"))
      (node (ref "R5") (pin "2") (pinfunction "2_2") (pintype "passive"))
      (node (ref "R6") (pin "2") (pinfunction "2_2") (pintype "passive"))
      (node (ref "R7") (pin "2") (pinfunction "2_2") (pintype "passive"))
      (node (ref "R8") (pin "2") (pinfunction "2_2") (pintype "passive"))
    )
    (net (code "39") (name "/VGA_HSYNC") (class "Default")
      (node (ref "J1") (pin "13") (pinfunction "13_13") (pintype "passive"))
      (node (ref "R13") (pin "2") (pinfunction "2_2") (pintype "passive"))
    )
    (net (code "40") (name "/VGA_R0") (class "Default")
      (node (ref "R1") (pin "1") (pinfunction "1_1") (pintype "passive"))
      (node (ref "U1") (pin "A11") (pinfunction "IO_L4N_T0_15_A11") (pintype "passive"))
    )
    (net (code "41") (name "/VGA_R1") (class "Default")
      (node (ref "R2") (pin "1") (pinfunction "1_1") (pintype "passive"))
      (node (ref "U1") (pin "B11") (pinfunction "IO_L4P_T0_15_B11") (pintype "passive"))
    )
    (net (code "42") (name "/VGA_R2") (class "Default")
      (node (ref "R3") (pin "1") (pinfunction "1_1") (pintype "passive"))
      (node (ref "U1") (pin "D12") (pinfunction "IO_L6P_T0_15_D12") (pintype "passive"))
    )
    (net (code "43") (name "/VGA_R3") (class "Default")
      (node (ref "R4") (pin "1") (pinfunction "1_1") (pintype "passive"))
      (node (ref "U1") (pin "H14") (pinfunction "IO_L15P_T2_DQS_15_H14") (pintype "passive"))
    )
    (net (code "44") (name "/VGA_R_ANALOG") (class "Default")
      (node (ref "J1") (pin "1") (pinfunction "1_1") (pintype "passive"))
      (node (ref "R1") (pin "2") (pinfunction "2_2") (pintype "passive"))
      (node (ref "R2") (pin "2") (pinfunction "2_2") (pintype "passive"))
      (node (ref "R3") (pin "2") (pinfunction "2_2") (pintype "passive"))
      (node (ref "R4") (pin "2") (pinfunction "2_2") (pintype "passive"))
    )
    (net (code "45") (name "/VGA_VSYNC") (class "Default")
      (node (ref "J1") (pin "14") (pinfunction "14_14") (pintype "passive"))
      (node (ref "R14") (pin "2") (pinfunction "2_2") (pintype "passive"))
    )
    (net (code "46") (name "/VIN") (class "Default")
      (node (ref "C44") (pin "2") (pinfunction "2_2") (pintype "passive"))
      (node (ref "C48") (pin "2") (pinfunction "2_2") (pintype "passive"))
      (node (ref "C49") (pin "2") (pinfunction "2_2") (pintype "passive"))
      (node (ref "C54") (pin "2") (pinfunction "2_2") (pintype "passive"))
      (node (ref "C55") (pin "2") (pinfunction "2_2") (pintype "passive"))
      (node (ref "C62") (pin "2") (pinfunction "2_2") (pintype "passive"))
      (node (ref "C64") (pin "1") (pinfunction "1_1") (pintype "passive"))
      (node (ref "C65") (pin "2") (pinfunction "2_2") (pintype "passive"))
      (node (ref "J3") (pin "1") (pinfunction "1_1") (pintype "passive"))
      (node (ref "U3") (pin "10") (pinfunction "AVIN_10") (pintype "input"))
      (node (ref "U3") (pin "11") (pinfunction "PVIN_11") (pintype "input"))
      (node (ref "U3") (pin "12") (pinfunction "PVIN_12") (pintype "input"))
      (node (ref "U3") (pin "13") (pinfunction "EN_13") (pintype "input"))
      (node (ref "U4") (pin "10") (pinfunction "AVIN_10") (pintype "input"))
      (node (ref "U4") (pin "11") (pinfunction "PVIN_11") (pintype "input"))
      (node (ref "U4") (pin "12") (pinfunction "PVIN_12") (pintype "input"))
      (node (ref "U4") (pin "13") (pinfunction "EN_13") (pintype "input"))
      (node (ref "U5") (pin "10") (pinfunction "AVIN_10") (pintype "input"))
      (node (ref "U5") (pin "11") (pinfunction "PVIN_11") (pintype "input"))
      (node (ref "U5") (pin "12") (pinfunction "PVIN_12") (pintype "input"))
      (node (ref "U5") (pin "13") (pinfunction "EN_13") (pintype "input"))
    )
    (net (code "47") (name "/VSYNC") (class "Default")
      (node (ref "R14") (pin "1") (pinfunction "1_1") (pintype "passive"))
      (node (ref "U1") (pin "F16") (pinfunction "IO_L14N_T2_SRCC_15_F16") (pintype "passive"))
    )
    (net (code "48") (name "GND") (class "Default")
      (node (ref "C1") (pin "2") (pinfunction "2_2") (pintype "passive"))
      (node (ref "C10") (pin "1") (pinfunction "1_1") (pintype "passive"))
      (node (ref "C11") (pin "1") (pinfunction "1_1") (pintype "passive"))
      (node (ref "C12") (pin "1") (pinfunction "1_1") (pintype "passive"))
      (node (ref "C13") (pin "1") (pinfunction "1_1") (pintype "passive"))
      (node (ref "C14") (pin "1") (pinfunction "1_1") (pintype "passive"))
      (node (ref "C15") (pin "1") (pinfunction "1_1") (pintype "passive"))
      (node (ref "C16") (pin "2") (pinfunction "2_2") (pintype "passive"))
      (node (ref "C17") (pin "2") (pinfunction "2_2") (pintype "passive"))
      (node (ref "C18") (pin "1") (pinfunction "1_1") (pintype "passive"))
      (node (ref "C19") (pin "1") (pinfunction "1_1") (pintype "passive"))
      (node (ref "C2") (pin "2") (pinfunction "2_2") (pintype "passive"))
      (node (ref "C20") (pin "1") (pinfunction "1_1") (pintype "passive"))
      (node (ref "C21") (pin "1") (pinfunction "1_1") (pintype "passive"))
      (node (ref "C22") (pin "1") (pinfunction "1_1") (pintype "passive"))
      (node (ref "C23") (pin "1") (pinfunction "1_1") (pintype "passive"))
      (node (ref "C24") (pin "1") (pinfunction "1_1") (pintype "passive"))
      (node (ref "C25") (pin "1") (pinfunction "1_1") (pintype "passive"))
      (node (ref "C26") (pin "1") (pinfunction "1_1") (pintype "passive"))
      (node (ref "C27") (pin "1") (pinfunction "1_1") (pintype "passive"))
      (node (ref "C28") (pin "1") (pinfunction "1_1") (pintype "passive"))
      (node (ref "C29") (pin "2") (pinfunction "2_2") (pintype "passive"))
      (node (ref "C3") (pin "2") (pinfunction "2_2") (pintype "passive"))
      (node (ref "C30") (pin "1") (pinfunction "1_1") (pintype "passive"))
      (node (ref "C31") (pin "2") (pinfunction "2_2") (pintype "passive"))
      (node (ref "C32") (pin "2") (pinfunction "2_2") (pintype "passive"))
      (node (ref "C33") (pin "2") (pinfunction "2_2") (pintype "passive"))
      (node (ref "C34") (pin "2") (pinfunction "2_2") (pintype "passive"))
      (node (ref "C35") (pin "2") (pinfunction "2_2") (pintype "passive"))
      (node (ref "C36") (pin "2") (pinfunction "2_2") (pintype "passive"))
      (node (ref "C37") (pin "2") (pinfunction "2_2") (pintype "passive"))
      (node (ref "C38") (pin "2") (pinfunction "2_2") (pintype "passive"))
      (node (ref "C39") (pin "2") (pinfunction "2_2") (pintype "passive"))
      (node (ref "C4") (pin "2") (pinfunction "2_2") (pintype "passive"))
      (node (ref "C40") (pin "2") (pinfunction "2_2") (pintype "passive"))
      (node (ref "C41") (pin "2") (pinfunction "2_2") (pintype "passive"))
      (node (ref "C42") (pin "2") (pinfunction "2_2") (pintype "passive"))
      (node (ref "C44") (pin "1") (pinfunction "1_1") (pintype "passive"))
      (node (ref "C45") (pin "1") (pinfunction "1_1") (pintype "passive"))
      (node (ref "C46") (pin "1") (pinfunction "1_1") (pintype "passive"))
      (node (ref "C47") (pin "1") (pinfunction "1_1") (pintype "passive"))
      (node (ref "C48") (pin "1") (pinfunction "1_1") (pintype "passive"))
      (node (ref "C49") (pin "1") (pinfunction "1_1") (pintype "passive"))
      (node (ref "C5") (pin "2") (pinfunction "2_2") (pintype "passive"))
      (node (ref "C50") (pin "1") (pinfunction "1_1") (pintype "passive"))
      (node (ref "C51") (pin "1") (pinfunction "1_1") (pintype "passive"))
      (node (ref "C52") (pin "1") (pinfunction "1_1") (pintype "passive"))
      (node (ref "C53") (pin "1") (pinfunction "1_1") (pintype "passive"))
      (node (ref "C54") (pin "1") (pinfunction "1_1") (pintype "passive"))
      (node (ref "C55") (pin "1") (pinfunction "1_1") (pintype "passive"))
      (node (ref "C56") (pin "1") (pinfunction "1_1") (pintype "passive"))
      (node (ref "C57") (pin "1") (pinfunction "1_1") (pintype "passive"))
      (node (ref "C59") (pin "2") (pinfunction "2_2") (pintype "passive"))
      (node (ref "C6") (pin "1") (pinfunction "1_1") (pintype "passive"))
      (node (ref "C60") (pin "1") (pinfunction "1_1") (pintype "passive"))
      (node (ref "C61") (pin "2") (pinfunction "2_2") (pintype "passive"))
      (node (ref "C62") (pin "1") (pinfunction "1_1") (pintype "passive"))
      (node (ref "C63") (pin "1") (pinfunction "1_1") (pintype "passive"))
      (node (ref "C64") (pin "2") (pinfunction "2_2") (pintype "passive"))
      (node (ref "C65") (pin "1") (pinfunction "1_1") (pintype "passive"))
      (node (ref "C66") (pin "1") (pinfunction "1_1") (pintype "passive"))
      (node (ref "C7") (pin "2") (pinfunction "2_2") (pintype "passive"))
      (node (ref "C8") (pin "2") (pinfunction "2_2") (pintype "passive"))
      (node (ref "C9") (pin "2") (pinfunction "2_2") (pintype "passive"))
      (node (ref "J1") (pin "10") (pinfunction "10_10") (pintype "passive"))
      (node (ref "J1") (pin "11") (pinfunction "11_11") (pintype "passive"))
      (node (ref "J1") (pin "12") (pinfunction "12_12") (pintype "passive"))
      (node (ref "J1") (pin "15") (pinfunction "15_15") (pintype "passive"))
      (node (ref "J1") (pin "4") (pinfunction "4_4") (pintype "passive"))
      (node (ref "J1") (pin "5") (pinfunction "5_5") (pintype "passive"))
      (node (ref "J1") (pin "6") (pinfunction "6_6") (pintype "passive"))
      (node (ref "J1") (pin "7") (pinfunction "7_7") (pintype "passive"))
      (node (ref "J1") (pin "8") (pinfunction "8_8") (pintype "passive"))
      (node (ref "J1") (pin "9") (pinfunction "9_9") (pintype "passive"))
      (node (ref "J1") (pin "M1") (pinfunction "M1_M1") (pintype "passive"))
      (node (ref "J1") (pin "M2") (pinfunction "M2_M2") (pintype "passive"))
      (node (ref "J2") (pin "10") (pinfunction "10_10") (pintype "passive"))
      (node (ref "J2") (pin "2") (pinfunction "2_2") (pintype "passive"))
      (node (ref "J2") (pin "4") (pinfunction "4_4") (pintype "passive"))
      (node (ref "J2") (pin "6") (pinfunction "6_6") (pintype "passive"))
      (node (ref "J2") (pin "8") (pinfunction "8_8") (pintype "passive"))
      (node (ref "J3") (pin "2") (pinfunction "2_2") (pintype "passive"))
      (node (ref "R20") (pin "2") (pinfunction "2_2") (pintype "passive"))
      (node (ref "R21") (pin "2") (pinfunction "2_2") (pintype "passive"))
      (node (ref "R26") (pin "2") (pinfunction "2_2") (pintype "passive"))
      (node (ref "R29") (pin "2") (pinfunction "2_2") (pintype "passive"))
      (node (ref "R31") (pin "2") (pinfunction "2_2") (pintype "passive"))
      (node (ref "SW1") (pin "3") (pinfunction "3_3") (pintype "passive"))
      (node (ref "U1") (pin "A12") (pinfunction "GND_2_A12") (pintype "passive"))
      (node (ref "U1") (pin "A2") (pinfunction "GND_1_A2") (pintype "passive"))
      (node (ref "U1") (pin "B15") (pinfunction "GND_4_B15") (pintype "passive"))
      (node (ref "U1") (pin "B5") (pinfunction "GND_3_B5") (pintype "passive"))
      (node (ref "U1") (pin "C18") (pinfunction "GND_6_C18") (pintype "passive"))
      (node (ref "U1") (pin "C8") (pinfunction "GND_5_C8") (pintype "passive"))
      (node (ref "U1") (pin "D1") (pinfunction "GND_7_D1") (pintype "passive"))
      (node (ref "U1") (pin "D11") (pinfunction "GND_8_D11") (pintype "passive"))
      (node (ref "U1") (pin "E14") (pinfunction "GND_10_E14") (pintype "passive"))
      (node (ref "U1") (pin "E4") (pinfunction "GND_9_E4") (pintype "passive"))
      (node (ref "U1") (pin "E8") (pinfunction "VCCBATT_0_E8") (pintype "passive"))
      (node (ref "U1") (pin "F11") (pinfunction "GND_13_F11") (pintype "passive"))
      (node (ref "U1") (pin "F17") (pinfunction "GND_14_F17") (pintype "passive"))
      (node (ref "U1") (pin "F7") (pinfunction "GND_11_F7") (pintype "passive"))
      (node (ref "U1") (pin "F9") (pinfunction "GND_12_F9") (pintype "passive"))
      (node (ref "U1") (pin "G10") (pinfunction "GND_16_G10") (pintype "passive"))
      (node (ref "U1") (pin "G12") (pinfunction "GND_17_G12") (pintype "passive"))
      (node (ref "U1") (pin "G8") (pinfunction "GND_15_G8") (pintype "passive"))
      (node (ref "U1") (pin "H11") (pinfunction "GND_20_H11") (pintype "passive"))
      (node (ref "U1") (pin "H13") (pinfunction "GND_21_H13") (pintype "passive"))
      (node (ref "U1") (pin "H3") (pinfunction "GND_18_H3") (pintype "passive"))
      (node (ref "U1") (pin "H7") (pinfunction "GND_19_H7") (pintype "passive"))
      (node (ref "U1") (pin "H9") (pinfunction "GNDADC_0_H9") (pintype "passive"))
      (node (ref "U1") (pin "J10") (pinfunction "VP_0_J10") (pintype "passive"))
      (node (ref "U1") (pin "J12") (pinfunction "GND_24_J12") (pintype "passive"))
      (node (ref "U1") (pin "J16") (pinfunction "GND_25_J16") (pintype "passive"))
      (node (ref "U1") (pin "J6") (pinfunction "GND_22_J6") (pintype "passive"))
      (node (ref "U1") (pin "J8") (pinfunction "GND_23_J8") (pintype "passive"))
      (node (ref "U1") (pin "K11") (pinfunction "GND_27_K11") (pintype "passive"))
      (node (ref "U1") (pin "K7") (pinfunction "GND_26_K7") (pintype "passive"))
      (node (ref "U1") (pin "K9") (pinfunction "VN_0_K9") (pintype "passive"))
      (node (ref "U1") (pin "L12") (pinfunction "GND_30_L12") (pintype "passive"))
      (node (ref "U1") (pin "L2") (pinfunction "GND_28_L2") (pintype "passive"))
      (node (ref "U1") (pin "L8") (pinfunction "GND_29_L8") (pintype "passive"))
      (node (ref "U1") (pin "M11") (pinfunction "GND_34_M11") (pintype "passive"))
      (node (ref "U1") (pin "M15") (pinfunction "GND_35_M15") (pintype "passive"))
      (node (ref "U1") (pin "M5") (pinfunction "GND_31_M5") (pintype "passive"))
      (node (ref "U1") (pin "M7") (pinfunction "GND_32_M7") (pintype "passive"))
      (node (ref "U1") (pin "M9") (pinfunction "GND_33_M9") (pintype "passive"))
      (node (ref "U1") (pin "N10") (pinfunction "GND_37_N10") (pintype "passive"))
      (node (ref "U1") (pin "N12") (pinfunction "GND_38_N12") (pintype "passive"))
      (node (ref "U1") (pin "N18") (pinfunction "GND_39_N18") (pintype "passive"))
      (node (ref "U1") (pin "N8") (pinfunction "GND_36_N8") (pintype "passive"))
      (node (ref "U1") (pin "P1") (pinfunction "GND_40_P1") (pintype "passive"))
      (node (ref "U1") (pin "R14") (pinfunction "GND_42_R14") (pintype "passive"))
      (node (ref "U1") (pin "R4") (pinfunction "GND_41_R4") (pintype "passive"))
      (node (ref "U1") (pin "T17") (pinfunction "GND_44_T17") (pintype "passive"))
      (node (ref "U1") (pin "T7") (pinfunction "GND_43_T7") (pintype "passive"))
      (node (ref "U1") (pin "U10") (pinfunction "GND_45_U10") (pintype "passive"))
      (node (ref "U1") (pin "V13") (pinfunction "GND_47_V13") (pintype "passive"))
      (node (ref "U1") (pin "V3") (pinfunction "GND_46_V3") (pintype "passive"))
      (node (ref "U2") (pin "4") (pinfunction "VSS_4") (pintype "power_in"))
      (node (ref "U3") (pin "15") (pinfunction "PGND_15") (pintype "power_in"))
      (node (ref "U3") (pin "16") (pinfunction "PGND_16") (pintype "power_in"))
      (node (ref "U3") (pin "17") (pinfunction "Exposed_Thermal_Pad_17") (pintype "power_in"))
      (node (ref "U3") (pin "6") (pinfunction "AGND_6") (pintype "power_in"))
      (node (ref "U3") (pin "7") (pinfunction "FSW_7") (pintype "input"))
      (node (ref "U3") (pin "8") (pinfunction "DEF_8") (pintype "input"))
      (node (ref "U4") (pin "15") (pinfunction "PGND_15") (pintype "power_in"))
      (node (ref "U4") (pin "16") (pinfunction "PGND_16") (pintype "power_in"))
      (node (ref "U4") (pin "17") (pinfunction "Exposed_Thermal_Pad_17") (pintype "power_in"))
      (node (ref "U4") (pin "6") (pinfunction "AGND_6") (pintype "power_in"))
      (node (ref "U4") (pin "7") (pinfunction "FSW_7") (pintype "input"))
      (node (ref "U4") (pin "8") (pinfunction "DEF_8") (pintype "input"))
      (node (ref "U5") (pin "15") (pinfunction "PGND_15") (pintype "power_in"))
      (node (ref "U5") (pin "16") (pinfunction "PGND_16") (pintype "power_in"))
      (node (ref "U5") (pin "17") (pinfunction "Exposed_Thermal_Pad_17") (pintype "power_in"))
      (node (ref "U5") (pin "6") (pinfunction "AGND_6") (pintype "power_in"))
      (node (ref "U5") (pin "7") (pinfunction "FSW_7") (pintype "input"))
      (node (ref "U5") (pin "8") (pinfunction "DEF_8") (pintype "input"))
      (node (ref "X1") (pin "2") (pinfunction "GND_2") (pintype "power_in"))
    )
    (net (code "49") (name "Net-(U1-DONE_0)") (class "Default")
      (node (ref "R24") (pin "1") (pinfunction "1_1") (pintype "passive"))
      (node (ref "U1") (pin "P10") (pinfunction "DONE_0_P10") (pintype "passive"))
    )
    (net (code "50") (name "Net-(U1-INIT_B_0)") (class "Default")
      (node (ref "R23") (pin "1") (pinfunction "1_1") (pintype "passive"))
      (node (ref "U1") (pin "P7") (pinfunction "INIT_B_0_P7") (pintype "passive"))
    )
    (net (code "51") (name "Net-(U1-M0_0)") (class "Default")
      (node (ref "R19") (pin "1") (pinfunction "1_1") (pintype "passive"))
      (node (ref "U1") (pin "P12") (pinfunction "M0_0_P12") (pintype "passive"))
    )
    (net (code "52") (name "Net-(U1-M1_0)") (class "Default")
      (node (ref "R20") (pin "1") (pinfunction "1_1") (pintype "passive"))
      (node (ref "U1") (pin "P13") (pinfunction "M1_0_P13") (pintype "passive"))
    )
    (net (code "53") (name "Net-(U1-M2_0)") (class "Default")
      (node (ref "R21") (pin "1") (pinfunction "1_1") (pintype "passive"))
      (node (ref "U1") (pin "P11") (pinfunction "M2_0_P11") (pintype "passive"))
    )
    (net (code "54") (name "Net-(U1-PROGRAM_B_0)") (class "Default")
      (node (ref "R22") (pin "1") (pinfunction "1_1") (pintype "passive"))
      (node (ref "U1") (pin "P9") (pinfunction "PROGRAM_B_0_P9") (pintype "passive"))
    )
    (net (code "55") (name "unconnected-(U1-DXN_0-PadL9)") (class "Default")
      (node (ref "U1") (pin "L9") (pinfunction "DXN_0_L9") (pintype "passive"))
    )
    (net (code "56") (name "unconnected-(U1-DXP_0-PadL10)") (class "Default")
      (node (ref "U1") (pin "L10") (pinfunction "DXP_0_L10") (pintype "passive"))
    )
    (net (code "57") (name "unconnected-(U1-IO_0_14-PadR11)") (class "Default")
      (node (ref "U1") (pin "R11") (pinfunction "IO_0_14_R11") (pintype "passive"))
    )
    (net (code "58") (name "unconnected-(U1-IO_0_34-PadK6)") (class "Default")
      (node (ref "U1") (pin "K6") (pinfunction "IO_0_34_K6") (pintype "passive"))
    )
    (net (code "59") (name "unconnected-(U1-IO_0_35-PadF5)") (class "Default")
      (node (ref "U1") (pin "F5") (pinfunction "IO_0_35_F5") (pintype "passive"))
    )
    (net (code "60") (name "unconnected-(U1-IO_25_14-PadR10)") (class "Default")
      (node (ref "U1") (pin "R10") (pinfunction "IO_25_14_R10") (pintype "passive"))
    )
    (net (code "61") (name "unconnected-(U1-IO_25_34-PadU8)") (class "Default")
      (node (ref "U1") (pin "U8") (pinfunction "IO_25_34_U8") (pintype "passive"))
    )
    (net (code "62") (name "unconnected-(U1-IO_25_35-PadJ5)") (class "Default")
      (node (ref "U1") (pin "J5") (pinfunction "IO_25_35_J5") (pintype "passive"))
    )
    (net (code "63") (name "unconnected-(U1-IO_L1N_T0_34-PadM1)") (class "Default")
      (node (ref "U1") (pin "M1") (pinfunction "IO_L1N_T0_34_M1") (pintype "passive"))
    )
    (net (code "64") (name "unconnected-(U1-IO_L1N_T0_AD0N_15-PadC14)") (class "Default")
      (node (ref "U1") (pin "C14") (pinfunction "IO_L1N_T0_AD0N_15_C14") (pintype "passive"))
    )
    (net (code "65") (name "unconnected-(U1-IO_L1N_T0_AD4N_35-PadC5)") (class "Default")
      (node (ref "U1") (pin "C5") (pinfunction "IO_L1N_T0_AD4N_35_C5") (pintype "passive"))
    )
    (net (code "66") (name "unconnected-(U1-IO_L1P_T0_34-PadL1)") (class "Default")
      (node (ref "U1") (pin "L1") (pinfunction "IO_L1P_T0_34_L1") (pintype "passive"))
    )
    (net (code "67") (name "unconnected-(U1-IO_L1P_T0_AD0P_15-PadD14)") (class "Default")
      (node (ref "U1") (pin "D14") (pinfunction "IO_L1P_T0_AD0P_15_D14") (pintype "passive"))
    )
    (net (code "68") (name "unconnected-(U1-IO_L1P_T0_AD4P_35-PadC6)") (class "Default")
      (node (ref "U1") (pin "C6") (pinfunction "IO_L1P_T0_AD4P_35_C6") (pintype "passive"))
    )
    (net (code "69") (name "unconnected-(U1-IO_L2N_T0_34-PadL3)") (class "Default")
      (node (ref "U1") (pin "L3") (pinfunction "IO_L2N_T0_34_L3") (pintype "passive"))
    )
    (net (code "70") (name "unconnected-(U1-IO_L2N_T0_AD8N_15-PadB14)") (class "Default")
      (node (ref "U1") (pin "B14") (pinfunction "IO_L2N_T0_AD8N_15_B14") (pintype "passive"))
    )
    (net (code "71") (name "unconnected-(U1-IO_L2N_T0_AD12N_35-PadB6)") (class "Default")
      (node (ref "U1") (pin "B6") (pinfunction "IO_L2N_T0_AD12N_35_B6") (pintype "passive"))
    )
    (net (code "72") (name "unconnected-(U1-IO_L2P_T0_34-PadK3)") (class "Default")
      (node (ref "U1") (pin "K3") (pinfunction "IO_L2P_T0_34_K3") (pintype "passive"))
    )
    (net (code "73") (name "unconnected-(U1-IO_L2P_T0_AD8P_15-PadB13)") (class "Default")
      (node (ref "U1") (pin "B13") (pinfunction "IO_L2P_T0_AD8P_15_B13") (pintype "passive"))
    )
    (net (code "74") (name "unconnected-(U1-IO_L2P_T0_AD12P_35-PadB7)") (class "Default")
      (node (ref "U1") (pin "B7") (pinfunction "IO_L2P_T0_AD12P_35_B7") (pintype "passive"))
    )
    (net (code "75") (name "unconnected-(U1-IO_L3N_T0_DQS_34-PadN1)") (class "Default")
      (node (ref "U1") (pin "N1") (pinfunction "IO_L3N_T0_DQS_34_N1") (pintype "passive"))
    )
    (net (code "76") (name "unconnected-(U1-IO_L3N_T0_DQS_AD1N_15-PadB12)") (class "Default")
      (node (ref "U1") (pin "B12") (pinfunction "IO_L3N_T0_DQS_AD1N_15_B12") (pintype "passive"))
    )
    (net (code "77") (name "unconnected-(U1-IO_L3N_T0_DQS_AD5N_35-PadA5)") (class "Default")
      (node (ref "U1") (pin "A5") (pinfunction "IO_L3N_T0_DQS_AD5N_35_A5") (pintype "passive"))
    )
    (net (code "78") (name "unconnected-(U1-IO_L3N_T0_DQS_EMCCLK_14-PadL16)") (class "Default")
      (node (ref "U1") (pin "L16") (pinfunction "IO_L3N_T0_DQS_EMCCLK_14_L16") (pintype "passive"))
    )
    (net (code "79") (name "unconnected-(U1-IO_L3P_T0_DQS_34-PadN2)") (class "Default")
      (node (ref "U1") (pin "N2") (pinfunction "IO_L3P_T0_DQS_34_N2") (pintype "passive"))
    )
    (net (code "80") (name "unconnected-(U1-IO_L3P_T0_DQS_AD1P_15-PadC12)") (class "Default")
      (node (ref "U1") (pin "C12") (pinfunction "IO_L3P_T0_DQS_AD1P_15_C12") (pintype "passive"))
    )
    (net (code "81") (name "unconnected-(U1-IO_L3P_T0_DQS_AD5P_35-PadA6)") (class "Default")
      (node (ref "U1") (pin "A6") (pinfunction "IO_L3P_T0_DQS_AD5P_35_A6") (pintype "passive"))
    )
    (net (code "82") (name "unconnected-(U1-IO_L3P_T0_DQS_PUDC_B_14-PadL15)") (class "Default")
      (node (ref "U1") (pin "L15") (pinfunction "IO_L3P_T0_DQS_PUDC_B_14_L15") (pintype "passive"))
    )
    (net (code "83") (name "unconnected-(U1-IO_L4N_T0_34-PadM2)") (class "Default")
      (node (ref "U1") (pin "M2") (pinfunction "IO_L4N_T0_34_M2") (pintype "passive"))
    )
    (net (code "84") (name "unconnected-(U1-IO_L4N_T0_35-PadC7)") (class "Default")
      (node (ref "U1") (pin "C7") (pinfunction "IO_L4N_T0_35_C7") (pintype "passive"))
    )
    (net (code "85") (name "unconnected-(U1-IO_L4N_T0_D05_14-PadM18)") (class "Default")
      (node (ref "U1") (pin "M18") (pinfunction "IO_L4N_T0_D05_14_M18") (pintype "passive"))
    )
    (net (code "86") (name "unconnected-(U1-IO_L4P_T0_34-PadM3)") (class "Default")
      (node (ref "U1") (pin "M3") (pinfunction "IO_L4P_T0_34_M3") (pintype "passive"))
    )
    (net (code "87") (name "unconnected-(U1-IO_L4P_T0_35-PadD8)") (class "Default")
      (node (ref "U1") (pin "D8") (pinfunction "IO_L4P_T0_35_D8") (pintype "passive"))
    )
    (net (code "88") (name "unconnected-(U1-IO_L4P_T0_D04_14-PadL18)") (class "Default")
      (node (ref "U1") (pin "L18") (pinfunction "IO_L4P_T0_D04_14_L18") (pintype "passive"))
    )
    (net (code "89") (name "unconnected-(U1-IO_L5N_T0_34-PadL4)") (class "Default")
      (node (ref "U1") (pin "L4") (pinfunction "IO_L5N_T0_34_L4") (pintype "passive"))
    )
    (net (code "90") (name "unconnected-(U1-IO_L5N_T0_AD9N_15-PadF14)") (class "Default")
      (node (ref "U1") (pin "F14") (pinfunction "IO_L5N_T0_AD9N_15_F14") (pintype "passive"))
    )
    (net (code "91") (name "unconnected-(U1-IO_L5N_T0_AD13N_35-PadE5)") (class "Default")
      (node (ref "U1") (pin "E5") (pinfunction "IO_L5N_T0_AD13N_35_E5") (pintype "passive"))
    )
    (net (code "92") (name "unconnected-(U1-IO_L5N_T0_D07_14-PadR13)") (class "Default")
      (node (ref "U1") (pin "R13") (pinfunction "IO_L5N_T0_D07_14_R13") (pintype "passive"))
    )
    (net (code "93") (name "unconnected-(U1-IO_L5P_T0_34-PadK5)") (class "Default")
      (node (ref "U1") (pin "K5") (pinfunction "IO_L5P_T0_34_K5") (pintype "passive"))
    )
    (net (code "94") (name "unconnected-(U1-IO_L5P_T0_AD9P_15-PadF13)") (class "Default")
      (node (ref "U1") (pin "F13") (pinfunction "IO_L5P_T0_AD9P_15_F13") (pintype "passive"))
    )
    (net (code "95") (name "unconnected-(U1-IO_L5P_T0_AD13P_35-PadE6)") (class "Default")
      (node (ref "U1") (pin "E6") (pinfunction "IO_L5P_T0_AD13P_35_E6") (pintype "passive"))
    )
    (net (code "96") (name "unconnected-(U1-IO_L5P_T0_D06_14-PadR12)") (class "Default")
      (node (ref "U1") (pin "R12") (pinfunction "IO_L5P_T0_D06_14_R12") (pintype "passive"))
    )
    (net (code "97") (name "unconnected-(U1-IO_L6N_T0_D08_VREF_14-PadM13)") (class "Default")
      (node (ref "U1") (pin "M13") (pinfunction "IO_L6N_T0_D08_VREF_14_M13") (pintype "passive"))
    )
    (net (code "98") (name "unconnected-(U1-IO_L6N_T0_VREF_15-PadD13)") (class "Default")
      (node (ref "U1") (pin "D13") (pinfunction "IO_L6N_T0_VREF_15_D13") (pintype "passive"))
    )
    (net (code "99") (name "unconnected-(U1-IO_L6N_T0_VREF_16-PadD9)") (class "Default")
      (node (ref "U1") (pin "D9") (pinfunction "IO_L6N_T0_VREF_16_D9") (pintype "passive"))
    )
    (net (code "100") (name "unconnected-(U1-IO_L6N_T0_VREF_34-PadL5)") (class "Default")
      (node (ref "U1") (pin "L5") (pinfunction "IO_L6N_T0_VREF_34_L5") (pintype "passive"))
    )
    (net (code "101") (name "unconnected-(U1-IO_L6N_T0_VREF_35-PadD7)") (class "Default")
      (node (ref "U1") (pin "D7") (pinfunction "IO_L6N_T0_VREF_35_D7") (pintype "passive"))
    )
    (net (code "102") (name "unconnected-(U1-IO_L6P_T0_34-PadL6)") (class "Default")
      (node (ref "U1") (pin "L6") (pinfunction "IO_L6P_T0_34_L6") (pintype "passive"))
    )
    (net (code "103") (name "unconnected-(U1-IO_L6P_T0_35-PadE7)") (class "Default")
      (node (ref "U1") (pin "E7") (pinfunction "IO_L6P_T0_35_E7") (pintype "passive"))
    )
    (net (code "104") (name "unconnected-(U1-IO_L7N_T1_34-PadV1)") (class "Default")
      (node (ref "U1") (pin "V1") (pinfunction "IO_L7N_T1_34_V1") (pintype "passive"))
    )
    (net (code "105") (name "unconnected-(U1-IO_L7N_T1_AD2N_15-PadB17)") (class "Default")
      (node (ref "U1") (pin "B17") (pinfunction "IO_L7N_T1_AD2N_15_B17") (pintype "passive"))
    )
    (net (code "106") (name "unconnected-(U1-IO_L7N_T1_AD6N_35-PadB4)") (class "Default")
      (node (ref "U1") (pin "B4") (pinfunction "IO_L7N_T1_AD6N_35_B4") (pintype "passive"))
    )
    (net (code "107") (name "unconnected-(U1-IO_L7N_T1_D10_14-PadT18)") (class "Default")
      (node (ref "U1") (pin "T18") (pinfunction "IO_L7N_T1_D10_14_T18") (pintype "passive"))
    )
    (net (code "108") (name "unconnected-(U1-IO_L7P_T1_34-PadU1)") (class "Default")
      (node (ref "U1") (pin "U1") (pinfunction "IO_L7P_T1_34_U1") (pintype "passive"))
    )
    (net (code "109") (name "unconnected-(U1-IO_L7P_T1_AD2P_15-PadB16)") (class "Default")
      (node (ref "U1") (pin "B16") (pinfunction "IO_L7P_T1_AD2P_15_B16") (pintype "passive"))
    )
    (net (code "110") (name "unconnected-(U1-IO_L7P_T1_AD6P_35-PadC4)") (class "Default")
      (node (ref "U1") (pin "C4") (pinfunction "IO_L7P_T1_AD6P_35_C4") (pintype "passive"))
    )
    (net (code "111") (name "unconnected-(U1-IO_L7P_T1_D09_14-PadR18)") (class "Default")
      (node (ref "U1") (pin "R18") (pinfunction "IO_L7P_T1_D09_14_R18") (pintype "passive"))
    )
    (net (code "112") (name "unconnected-(U1-IO_L8N_T1_34-PadU3)") (class "Default")
      (node (ref "U1") (pin "U3") (pinfunction "IO_L8N_T1_34_U3") (pintype "passive"))
    )
    (net (code "113") (name "unconnected-(U1-IO_L8N_T1_AD10N_15-PadA16)") (class "Default")
      (node (ref "U1") (pin "A16") (pinfunction "IO_L8N_T1_AD10N_15_A16") (pintype "passive"))
    )
    (net (code "114") (name "unconnected-(U1-IO_L8N_T1_AD14N_35-PadA3)") (class "Default")
      (node (ref "U1") (pin "A3") (pinfunction "IO_L8N_T1_AD14N_35_A3") (pintype "passive"))
    )
    (net (code "115") (name "unconnected-(U1-IO_L8N_T1_D12_14-PadP14)") (class "Default")
      (node (ref "U1") (pin "P14") (pinfunction "IO_L8N_T1_D12_14_P14") (pintype "passive"))
    )
    (net (code "116") (name "unconnected-(U1-IO_L8P_T1_34-PadU4)") (class "Default")
      (node (ref "U1") (pin "U4") (pinfunction "IO_L8P_T1_34_U4") (pintype "passive"))
    )
    (net (code "117") (name "unconnected-(U1-IO_L8P_T1_AD10P_15-PadA15)") (class "Default")
      (node (ref "U1") (pin "A15") (pinfunction "IO_L8P_T1_AD10P_15_A15") (pintype "passive"))
    )
    (net (code "118") (name "unconnected-(U1-IO_L8P_T1_AD14P_35-PadA4)") (class "Default")
      (node (ref "U1") (pin "A4") (pinfunction "IO_L8P_T1_AD14P_35_A4") (pintype "passive"))
    )
    (net (code "119") (name "unconnected-(U1-IO_L8P_T1_D11_14-PadN14)") (class "Default")
      (node (ref "U1") (pin "N14") (pinfunction "IO_L8P_T1_D11_14_N14") (pintype "passive"))
    )
    (net (code "120") (name "unconnected-(U1-IO_L9N_T1_DQS_34-PadV2)") (class "Default")
      (node (ref "U1") (pin "V2") (pinfunction "IO_L9N_T1_DQS_34_V2") (pintype "passive"))
    )
    (net (code "121") (name "unconnected-(U1-IO_L9N_T1_DQS_AD3N_15-PadA14)") (class "Default")
      (node (ref "U1") (pin "A14") (pinfunction "IO_L9N_T1_DQS_AD3N_15_A14") (pintype "passive"))
    )
    (net (code "122") (name "unconnected-(U1-IO_L9N_T1_DQS_AD7N_35-PadA1)") (class "Default")
      (node (ref "U1") (pin "A1") (pinfunction "IO_L9N_T1_DQS_AD7N_35_A1") (pintype "passive"))
    )
    (net (code "123") (name "unconnected-(U1-IO_L9N_T1_DQS_D13_14-PadP18)") (class "Default")
      (node (ref "U1") (pin "P18") (pinfunction "IO_L9N_T1_DQS_D13_14_P18") (pintype "passive"))
    )
    (net (code "124") (name "unconnected-(U1-IO_L9P_T1_DQS_14-PadN17)") (class "Default")
      (node (ref "U1") (pin "N17") (pinfunction "IO_L9P_T1_DQS_14_N17") (pintype "passive"))
    )
    (net (code "125") (name "unconnected-(U1-IO_L9P_T1_DQS_34-PadU2)") (class "Default")
      (node (ref "U1") (pin "U2") (pinfunction "IO_L9P_T1_DQS_34_U2") (pintype "passive"))
    )
    (net (code "126") (name "unconnected-(U1-IO_L9P_T1_DQS_AD3P_15-PadA13)") (class "Default")
      (node (ref "U1") (pin "A13") (pinfunction "IO_L9P_T1_DQS_AD3P_15_A13") (pintype "passive"))
    )
    (net (code "127") (name "unconnected-(U1-IO_L9P_T1_DQS_AD7P_35-PadB1)") (class "Default")
      (node (ref "U1") (pin "B1") (pinfunction "IO_L9P_T1_DQS_AD7P_35_B1") (pintype "passive"))
    )
    (net (code "128") (name "unconnected-(U1-IO_L10N_T1_34-PadV4)") (class "Default")
      (node (ref "U1") (pin "V4") (pinfunction "IO_L10N_T1_34_V4") (pintype "passive"))
    )
    (net (code "129") (name "unconnected-(U1-IO_L10N_T1_AD11N_15-PadA18)") (class "Default")
      (node (ref "U1") (pin "A18") (pinfunction "IO_L10N_T1_AD11N_15_A18") (pintype "passive"))
    )
    (net (code "130") (name "unconnected-(U1-IO_L10N_T1_AD15N_35-PadB2)") (class "Default")
      (node (ref "U1") (pin "B2") (pinfunction "IO_L10N_T1_AD15N_35_B2") (pintype "passive"))
    )
    (net (code "131") (name "unconnected-(U1-IO_L10N_T1_D15_14-PadM17)") (class "Default")
      (node (ref "U1") (pin "M17") (pinfunction "IO_L10N_T1_D15_14_M17") (pintype "passive"))
    )
    (net (code "132") (name "unconnected-(U1-IO_L10P_T1_34-PadV5)") (class "Default")
      (node (ref "U1") (pin "V5") (pinfunction "IO_L10P_T1_34_V5") (pintype "passive"))
    )
    (net (code "133") (name "unconnected-(U1-IO_L10P_T1_AD11P_15-PadB18)") (class "Default")
      (node (ref "U1") (pin "B18") (pinfunction "IO_L10P_T1_AD11P_15_B18") (pintype "passive"))
    )
    (net (code "134") (name "unconnected-(U1-IO_L10P_T1_AD15P_35-PadB3)") (class "Default")
      (node (ref "U1") (pin "B3") (pinfunction "IO_L10P_T1_AD15P_35_B3") (pintype "passive"))
    )
    (net (code "135") (name "unconnected-(U1-IO_L10P_T1_D14_14-PadM16)") (class "Default")
      (node (ref "U1") (pin "M16") (pinfunction "IO_L10P_T1_D14_14_M16") (pintype "passive"))
    )
    (net (code "136") (name "unconnected-(U1-IO_L11N_T1_SRCC_14-PadN16)") (class "Default")
      (node (ref "U1") (pin "N16") (pinfunction "IO_L11N_T1_SRCC_14_N16") (pintype "passive"))
    )
    (net (code "137") (name "unconnected-(U1-IO_L11N_T1_SRCC_16-PadB9)") (class "Default")
      (node (ref "U1") (pin "B9") (pinfunction "IO_L11N_T1_SRCC_16_B9") (pintype "passive"))
    )
    (net (code "138") (name "unconnected-(U1-IO_L11N_T1_SRCC_34-PadT3)") (class "Default")
      (node (ref "U1") (pin "T3") (pinfunction "IO_L11N_T1_SRCC_34_T3") (pintype "passive"))
    )
    (net (code "139") (name "unconnected-(U1-IO_L11N_T1_SRCC_35-PadD4)") (class "Default")
      (node (ref "U1") (pin "D4") (pinfunction "IO_L11N_T1_SRCC_35_D4") (pintype "passive"))
    )
    (net (code "140") (name "unconnected-(U1-IO_L11P_T1_SRCC_14-PadN15)") (class "Default")
      (node (ref "U1") (pin "N15") (pinfunction "IO_L11P_T1_SRCC_14_N15") (pintype "passive"))
    )
    (net (code "141") (name "unconnected-(U1-IO_L11P_T1_SRCC_16-PadC9)") (class "Default")
      (node (ref "U1") (pin "C9") (pinfunction "IO_L11P_T1_SRCC_16_C9") (pintype "passive"))
    )
    (net (code "142") (name "unconnected-(U1-IO_L11P_T1_SRCC_34-PadR3)") (class "Default")
      (node (ref "U1") (pin "R3") (pinfunction "IO_L11P_T1_SRCC_34_R3") (pintype "passive"))
    )
    (net (code "143") (name "unconnected-(U1-IO_L11P_T1_SRCC_35-PadD5)") (class "Default")
      (node (ref "U1") (pin "D5") (pinfunction "IO_L11P_T1_SRCC_35_D5") (pintype "passive"))
    )
    (net (code "144") (name "unconnected-(U1-IO_L12N_T1_MRCC_14-PadR17)") (class "Default")
      (node (ref "U1") (pin "R17") (pinfunction "IO_L12N_T1_MRCC_14_R17") (pintype "passive"))
    )
    (net (code "145") (name "unconnected-(U1-IO_L12N_T1_MRCC_16-PadA8)") (class "Default")
      (node (ref "U1") (pin "A8") (pinfunction "IO_L12N_T1_MRCC_16_A8") (pintype "passive"))
    )
    (net (code "146") (name "unconnected-(U1-IO_L12N_T1_MRCC_34-PadT4)") (class "Default")
      (node (ref "U1") (pin "T4") (pinfunction "IO_L12N_T1_MRCC_34_T4") (pintype "passive"))
    )
    (net (code "147") (name "unconnected-(U1-IO_L12N_T1_MRCC_35-PadD3)") (class "Default")
      (node (ref "U1") (pin "D3") (pinfunction "IO_L12N_T1_MRCC_35_D3") (pintype "passive"))
    )
    (net (code "148") (name "unconnected-(U1-IO_L12P_T1_MRCC_16-PadB8)") (class "Default")
      (node (ref "U1") (pin "B8") (pinfunction "IO_L12P_T1_MRCC_16_B8") (pintype "passive"))
    )
    (net (code "149") (name "unconnected-(U1-IO_L12P_T1_MRCC_34-PadT5)") (class "Default")
      (node (ref "U1") (pin "T5") (pinfunction "IO_L12P_T1_MRCC_34_T5") (pintype "passive"))
    )
    (net (code "150") (name "unconnected-(U1-IO_L12P_T1_MRCC_35-PadE3)") (class "Default")
      (node (ref "U1") (pin "E3") (pinfunction "IO_L12P_T1_MRCC_35_E3") (pintype "passive"))
    )
    (net (code "151") (name "unconnected-(U1-IO_L13N_T2_MRCC_14-PadR15)") (class "Default")
      (node (ref "U1") (pin "R15") (pinfunction "IO_L13N_T2_MRCC_14_R15") (pintype "passive"))
    )
    (net (code "152") (name "unconnected-(U1-IO_L13N_T2_MRCC_16-PadC10)") (class "Default")
      (node (ref "U1") (pin "C10") (pinfunction "IO_L13N_T2_MRCC_16_C10") (pintype "passive"))
    )
    (net (code "153") (name "unconnected-(U1-IO_L13N_T2_MRCC_34-PadP5)") (class "Default")
      (node (ref "U1") (pin "P5") (pinfunction "IO_L13N_T2_MRCC_34_P5") (pintype "passive"))
    )
    (net (code "154") (name "unconnected-(U1-IO_L13N_T2_MRCC_35-PadF3)") (class "Default")
      (node (ref "U1") (pin "F3") (pinfunction "IO_L13N_T2_MRCC_35_F3") (pintype "passive"))
    )
    (net (code "155") (name "unconnected-(U1-IO_L13P_T2_MRCC_14-PadP15)") (class "Default")
      (node (ref "U1") (pin "P15") (pinfunction "IO_L13P_T2_MRCC_14_P15") (pintype "passive"))
    )
    (net (code "156") (name "unconnected-(U1-IO_L13P_T2_MRCC_16-PadC11)") (class "Default")
      (node (ref "U1") (pin "C11") (pinfunction "IO_L13P_T2_MRCC_16_C11") (pintype "passive"))
    )
    (net (code "157") (name "unconnected-(U1-IO_L13P_T2_MRCC_34-PadN5)") (class "Default")
      (node (ref "U1") (pin "N5") (pinfunction "IO_L13P_T2_MRCC_34_N5") (pintype "passive"))
    )
    (net (code "158") (name "unconnected-(U1-IO_L13P_T2_MRCC_35-PadF4)") (class "Default")
      (node (ref "U1") (pin "F4") (pinfunction "IO_L13P_T2_MRCC_35_F4") (pintype "passive"))
    )
    (net (code "159") (name "unconnected-(U1-IO_L14N_T2_SRCC_14-PadT15)") (class "Default")
      (node (ref "U1") (pin "T15") (pinfunction "IO_L14N_T2_SRCC_14_T15") (pintype "passive"))
    )
    (net (code "160") (name "unconnected-(U1-IO_L14N_T2_SRCC_16-PadA9)") (class "Default")
      (node (ref "U1") (pin "A9") (pinfunction "IO_L14N_T2_SRCC_16_A9") (pintype "passive"))
    )
    (net (code "161") (name "unconnected-(U1-IO_L14N_T2_SRCC_34-PadP3)") (class "Default")
      (node (ref "U1") (pin "P3") (pinfunction "IO_L14N_T2_SRCC_34_P3") (pintype "passive"))
    )
    (net (code "162") (name "unconnected-(U1-IO_L14N_T2_SRCC_35-PadD2)") (class "Default")
      (node (ref "U1") (pin "D2") (pinfunction "IO_L14N_T2_SRCC_35_D2") (pintype "passive"))
    )
    (net (code "163") (name "unconnected-(U1-IO_L14P_T2_SRCC_14-PadT14)") (class "Default")
      (node (ref "U1") (pin "T14") (pinfunction "IO_L14P_T2_SRCC_14_T14") (pintype "passive"))
    )
    (net (code "164") (name "unconnected-(U1-IO_L14P_T2_SRCC_16-PadA10)") (class "Default")
      (node (ref "U1") (pin "A10") (pinfunction "IO_L14P_T2_SRCC_16_A10") (pintype "passive"))
    )
    (net (code "165") (name "unconnected-(U1-IO_L14P_T2_SRCC_34-PadP4)") (class "Default")
      (node (ref "U1") (pin "P4") (pinfunction "IO_L14P_T2_SRCC_34_P4") (pintype "passive"))
    )
    (net (code "166") (name "unconnected-(U1-IO_L14P_T2_SRCC_35-PadE2)") (class "Default")
      (node (ref "U1") (pin "E2") (pinfunction "IO_L14P_T2_SRCC_35_E2") (pintype "passive"))
    )
    (net (code "167") (name "unconnected-(U1-IO_L15N_T2_DQS_34-PadR2)") (class "Default")
      (node (ref "U1") (pin "R2") (pinfunction "IO_L15N_T2_DQS_34_R2") (pintype "passive"))
    )
    (net (code "168") (name "unconnected-(U1-IO_L15N_T2_DQS_35-PadG2)") (class "Default")
      (node (ref "U1") (pin "G2") (pinfunction "IO_L15N_T2_DQS_35_G2") (pintype "passive"))
    )
    (net (code "169") (name "unconnected-(U1-IO_L15N_T2_DQS_ADV_B_15-PadG14)") (class "Default")
      (node (ref "U1") (pin "G14") (pinfunction "IO_L15N_T2_DQS_ADV_B_15_G14") (pintype "passive"))
    )
    (net (code "170") (name "unconnected-(U1-IO_L15N_T2_DQS_DOUT_CSO_B_14-PadT16)") (class "Default")
      (node (ref "U1") (pin "T16") (pinfunction "IO_L15N_T2_DQS_DOUT_CSO_B_14_T16") (pintype "passive"))
    )
    (net (code "171") (name "unconnected-(U1-IO_L15P_T2_DQS_34-PadP2)") (class "Default")
      (node (ref "U1") (pin "P2") (pinfunction "IO_L15P_T2_DQS_34_P2") (pintype "passive"))
    )
    (net (code "172") (name "unconnected-(U1-IO_L15P_T2_DQS_35-PadH2)") (class "Default")
      (node (ref "U1") (pin "H2") (pinfunction "IO_L15P_T2_DQS_35_H2") (pintype "passive"))
    )
    (net (code "173") (name "unconnected-(U1-IO_L15P_T2_DQS_RDWR_B_14-PadR16)") (class "Default")
      (node (ref "U1") (pin "R16") (pinfunction "IO_L15P_T2_DQS_RDWR_B_14_R16") (pintype "passive"))
    )
    (net (code "174") (name "unconnected-(U1-IO_L16N_T2_34-PadN4)") (class "Default")
      (node (ref "U1") (pin "N4") (pinfunction "IO_L16N_T2_34_N4") (pintype "passive"))
    )
    (net (code "175") (name "unconnected-(U1-IO_L16N_T2_35-PadC1)") (class "Default")
      (node (ref "U1") (pin "C1") (pinfunction "IO_L16N_T2_35_C1") (pintype "passive"))
    )
    (net (code "176") (name "unconnected-(U1-IO_L16N_T2_A15_D31_14-PadV16)") (class "Default")
      (node (ref "U1") (pin "V16") (pinfunction "IO_L16N_T2_A15_D31_14_V16") (pintype "passive"))
    )
    (net (code "177") (name "unconnected-(U1-IO_L16N_T2_A27_15-PadD17)") (class "Default")
      (node (ref "U1") (pin "D17") (pinfunction "IO_L16N_T2_A27_15_D17") (pintype "passive"))
    )
    (net (code "178") (name "unconnected-(U1-IO_L16P_T2_34-PadM4)") (class "Default")
      (node (ref "U1") (pin "M4") (pinfunction "IO_L16P_T2_34_M4") (pintype "passive"))
    )
    (net (code "179") (name "unconnected-(U1-IO_L16P_T2_35-PadC2)") (class "Default")
      (node (ref "U1") (pin "C2") (pinfunction "IO_L16P_T2_35_C2") (pintype "passive"))
    )
    (net (code "180") (name "unconnected-(U1-IO_L16P_T2_A28_15-PadE17)") (class "Default")
      (node (ref "U1") (pin "E17") (pinfunction "IO_L16P_T2_A28_15_E17") (pintype "passive"))
    )
    (net (code "181") (name "unconnected-(U1-IO_L16P_T2_CSI_B_14-PadV15)") (class "Default")
      (node (ref "U1") (pin "V15") (pinfunction "IO_L16P_T2_CSI_B_14_V15") (pintype "passive"))
    )
    (net (code "182") (name "unconnected-(U1-IO_L17N_T2_34-PadT1)") (class "Default")
      (node (ref "U1") (pin "T1") (pinfunction "IO_L17N_T2_34_T1") (pintype "passive"))
    )
    (net (code "183") (name "unconnected-(U1-IO_L17N_T2_35-PadG1)") (class "Default")
      (node (ref "U1") (pin "G1") (pinfunction "IO_L17N_T2_35_G1") (pintype "passive"))
    )
    (net (code "184") (name "unconnected-(U1-IO_L17N_T2_A13_D29_14-PadU18)") (class "Default")
      (node (ref "U1") (pin "U18") (pinfunction "IO_L17N_T2_A13_D29_14_U18") (pintype "passive"))
    )
    (net (code "185") (name "unconnected-(U1-IO_L17N_T2_A25_15-PadJ13)") (class "Default")
      (node (ref "U1") (pin "J13") (pinfunction "IO_L17N_T2_A25_15_J13") (pintype "passive"))
    )
    (net (code "186") (name "unconnected-(U1-IO_L17P_T2_34-PadR1)") (class "Default")
      (node (ref "U1") (pin "R1") (pinfunction "IO_L17P_T2_34_R1") (pintype "passive"))
    )
    (net (code "187") (name "unconnected-(U1-IO_L17P_T2_35-PadH1)") (class "Default")
      (node (ref "U1") (pin "H1") (pinfunction "IO_L17P_T2_35_H1") (pintype "passive"))
    )
    (net (code "188") (name "unconnected-(U1-IO_L17P_T2_A14_D30_14-PadU17)") (class "Default")
      (node (ref "U1") (pin "U17") (pinfunction "IO_L17P_T2_A14_D30_14_U17") (pintype "passive"))
    )
    (net (code "189") (name "unconnected-(U1-IO_L17P_T2_A26_15-PadK13)") (class "Default")
      (node (ref "U1") (pin "K13") (pinfunction "IO_L17P_T2_A26_15_K13") (pintype "passive"))
    )
    (net (code "190") (name "unconnected-(U1-IO_L18N_T2_34-PadN6)") (class "Default")
      (node (ref "U1") (pin "N6") (pinfunction "IO_L18N_T2_34_N6") (pintype "passive"))
    )
    (net (code "191") (name "unconnected-(U1-IO_L18N_T2_35-PadE1)") (class "Default")
      (node (ref "U1") (pin "E1") (pinfunction "IO_L18N_T2_35_E1") (pintype "passive"))
    )
    (net (code "192") (name "unconnected-(U1-IO_L18N_T2_A11_D27_14-PadV17)") (class "Default")
      (node (ref "U1") (pin "V17") (pinfunction "IO_L18N_T2_A11_D27_14_V17") (pintype "passive"))
    )
    (net (code "193") (name "unconnected-(U1-IO_L18N_T2_A23_15-PadG17)") (class "Default")
      (node (ref "U1") (pin "G17") (pinfunction "IO_L18N_T2_A23_15_G17") (pintype "passive"))
    )
    (net (code "194") (name "unconnected-(U1-IO_L18P_T2_34-PadM6)") (class "Default")
      (node (ref "U1") (pin "M6") (pinfunction "IO_L18P_T2_34_M6") (pintype "passive"))
    )
    (net (code "195") (name "unconnected-(U1-IO_L18P_T2_35-PadF1)") (class "Default")
      (node (ref "U1") (pin "F1") (pinfunction "IO_L18P_T2_35_F1") (pintype "passive"))
    )
    (net (code "196") (name "unconnected-(U1-IO_L18P_T2_A12_D28_14-PadU16)") (class "Default")
      (node (ref "U1") (pin "U16") (pinfunction "IO_L18P_T2_A12_D28_14_U16") (pintype "passive"))
    )
    (net (code "197") (name "unconnected-(U1-IO_L18P_T2_A24_15-PadH17)") (class "Default")
      (node (ref "U1") (pin "H17") (pinfunction "IO_L18P_T2_A24_15_H17") (pintype "passive"))
    )
    (net (code "198") (name "unconnected-(U1-IO_L19N_T3_A09_D25_VREF_14-PadU11)") (class "Default")
      (node (ref "U1") (pin "U11") (pinfunction "IO_L19N_T3_A09_D25_VREF_14_U11") (pintype "passive"))
    )
    (net (code "199") (name "unconnected-(U1-IO_L19N_T3_A21_VREF_15-PadH15)") (class "Default")
      (node (ref "U1") (pin "H15") (pinfunction "IO_L19N_T3_A21_VREF_15_H15") (pintype "passive"))
    )
    (net (code "200") (name "unconnected-(U1-IO_L19N_T3_VREF_16-PadD10)") (class "Default")
      (node (ref "U1") (pin "D10") (pinfunction "IO_L19N_T3_VREF_16_D10") (pintype "passive"))
    )
    (net (code "201") (name "unconnected-(U1-IO_L19N_T3_VREF_34-PadR5)") (class "Default")
      (node (ref "U1") (pin "R5") (pinfunction "IO_L19N_T3_VREF_34_R5") (pintype "passive"))
    )
    (net (code "202") (name "unconnected-(U1-IO_L19N_T3_VREF_35-PadF6)") (class "Default")
      (node (ref "U1") (pin "F6") (pinfunction "IO_L19N_T3_VREF_35_F6") (pintype "passive"))
    )
    (net (code "203") (name "unconnected-(U1-IO_L19P_T3_34-PadR6)") (class "Default")
      (node (ref "U1") (pin "R6") (pinfunction "IO_L19P_T3_34_R6") (pintype "passive"))
    )
    (net (code "204") (name "unconnected-(U1-IO_L19P_T3_35-PadG6)") (class "Default")
      (node (ref "U1") (pin "G6") (pinfunction "IO_L19P_T3_35_G6") (pintype "passive"))
    )
    (net (code "205") (name "unconnected-(U1-IO_L19P_T3_A10_D26_14-PadT11)") (class "Default")
      (node (ref "U1") (pin "T11") (pinfunction "IO_L19P_T3_A10_D26_14_T11") (pintype "passive"))
    )
    (net (code "206") (name "unconnected-(U1-IO_L19P_T3_A22_15-PadJ14)") (class "Default")
      (node (ref "U1") (pin "J14") (pinfunction "IO_L19P_T3_A22_15_J14") (pintype "passive"))
    )
    (net (code "207") (name "unconnected-(U1-IO_L20N_T3_34-PadV6)") (class "Default")
      (node (ref "U1") (pin "V6") (pinfunction "IO_L20N_T3_34_V6") (pintype "passive"))
    )
    (net (code "208") (name "unconnected-(U1-IO_L20N_T3_35-PadG3)") (class "Default")
      (node (ref "U1") (pin "G3") (pinfunction "IO_L20N_T3_35_G3") (pintype "passive"))
    )
    (net (code "209") (name "unconnected-(U1-IO_L20N_T3_A07_D23_14-PadV12)") (class "Default")
      (node (ref "U1") (pin "V12") (pinfunction "IO_L20N_T3_A07_D23_14_V12") (pintype "passive"))
    )
    (net (code "210") (name "unconnected-(U1-IO_L20N_T3_A19_15-PadC17)") (class "Default")
      (node (ref "U1") (pin "C17") (pinfunction "IO_L20N_T3_A19_15_C17") (pintype "passive"))
    )
    (net (code "211") (name "unconnected-(U1-IO_L20P_T3_34-PadV7)") (class "Default")
      (node (ref "U1") (pin "V7") (pinfunction "IO_L20P_T3_34_V7") (pintype "passive"))
    )
    (net (code "212") (name "unconnected-(U1-IO_L20P_T3_35-PadG4)") (class "Default")
      (node (ref "U1") (pin "G4") (pinfunction "IO_L20P_T3_35_G4") (pintype "passive"))
    )
    (net (code "213") (name "unconnected-(U1-IO_L20P_T3_A08_D24_14-PadU12)") (class "Default")
      (node (ref "U1") (pin "U12") (pinfunction "IO_L20P_T3_A08_D24_14_U12") (pintype "passive"))
    )
    (net (code "214") (name "unconnected-(U1-IO_L20P_T3_A20_15-PadC16)") (class "Default")
      (node (ref "U1") (pin "C16") (pinfunction "IO_L20P_T3_A20_15_C16") (pintype "passive"))
    )
    (net (code "215") (name "unconnected-(U1-IO_L21N_T3_DQS_34-PadV9)") (class "Default")
      (node (ref "U1") (pin "V9") (pinfunction "IO_L21N_T3_DQS_34_V9") (pintype "passive"))
    )
    (net (code "216") (name "unconnected-(U1-IO_L21N_T3_DQS_35-PadH4)") (class "Default")
      (node (ref "U1") (pin "H4") (pinfunction "IO_L21N_T3_DQS_35_H4") (pintype "passive"))
    )
    (net (code "217") (name "unconnected-(U1-IO_L21N_T3_DQS_A06_D22_14-PadV11)") (class "Default")
      (node (ref "U1") (pin "V11") (pinfunction "IO_L21N_T3_DQS_A06_D22_14_V11") (pintype "passive"))
    )
    (net (code "218") (name "unconnected-(U1-IO_L21N_T3_DQS_A18_15-PadD18)") (class "Default")
      (node (ref "U1") (pin "D18") (pinfunction "IO_L21N_T3_DQS_A18_15_D18") (pintype "passive"))
    )
    (net (code "219") (name "unconnected-(U1-IO_L21P_T3_DQS_14-PadV10)") (class "Default")
      (node (ref "U1") (pin "V10") (pinfunction "IO_L21P_T3_DQS_14_V10") (pintype "passive"))
    )
    (net (code "220") (name "unconnected-(U1-IO_L21P_T3_DQS_34-PadU9)") (class "Default")
      (node (ref "U1") (pin "U9") (pinfunction "IO_L21P_T3_DQS_34_U9") (pintype "passive"))
    )
    (net (code "221") (name "unconnected-(U1-IO_L21P_T3_DQS_35-PadJ4)") (class "Default")
      (node (ref "U1") (pin "J4") (pinfunction "IO_L21P_T3_DQS_35_J4") (pintype "passive"))
    )
    (net (code "222") (name "unconnected-(U1-IO_L22N_T3_34-PadU6)") (class "Default")
      (node (ref "U1") (pin "U6") (pinfunction "IO_L22N_T3_34_U6") (pintype "passive"))
    )
    (net (code "223") (name "unconnected-(U1-IO_L22N_T3_35-PadJ2)") (class "Default")
      (node (ref "U1") (pin "J2") (pinfunction "IO_L22N_T3_35_J2") (pintype "passive"))
    )
    (net (code "224") (name "unconnected-(U1-IO_L22N_T3_A04_D20_14-PadV14)") (class "Default")
      (node (ref "U1") (pin "V14") (pinfunction "IO_L22N_T3_A04_D20_14_V14") (pintype "passive"))
    )
    (net (code "225") (name "unconnected-(U1-IO_L22N_T3_A16_15-PadF18)") (class "Default")
      (node (ref "U1") (pin "F18") (pinfunction "IO_L22N_T3_A16_15_F18") (pintype "passive"))
    )
    (net (code "226") (name "unconnected-(U1-IO_L22P_T3_34-PadU7)") (class "Default")
      (node (ref "U1") (pin "U7") (pinfunction "IO_L22P_T3_34_U7") (pintype "passive"))
    )
    (net (code "227") (name "unconnected-(U1-IO_L22P_T3_35-PadJ3)") (class "Default")
      (node (ref "U1") (pin "J3") (pinfunction "IO_L22P_T3_35_J3") (pintype "passive"))
    )
    (net (code "228") (name "unconnected-(U1-IO_L22P_T3_A05_D21_14-PadU14)") (class "Default")
      (node (ref "U1") (pin "U14") (pinfunction "IO_L22P_T3_A05_D21_14_U14") (pintype "passive"))
    )
    (net (code "229") (name "unconnected-(U1-IO_L22P_T3_A17_15-PadG18)") (class "Default")
      (node (ref "U1") (pin "G18") (pinfunction "IO_L22P_T3_A17_15_G18") (pintype "passive"))
    )
    (net (code "230") (name "unconnected-(U1-IO_L23N_T3_34-PadT6)") (class "Default")
      (node (ref "U1") (pin "T6") (pinfunction "IO_L23N_T3_34_T6") (pintype "passive"))
    )
    (net (code "231") (name "unconnected-(U1-IO_L23N_T3_35-PadK1)") (class "Default")
      (node (ref "U1") (pin "K1") (pinfunction "IO_L23N_T3_35_K1") (pintype "passive"))
    )
    (net (code "232") (name "unconnected-(U1-IO_L23N_T3_A02_D18_14-PadU13)") (class "Default")
      (node (ref "U1") (pin "U13") (pinfunction "IO_L23N_T3_A02_D18_14_U13") (pintype "passive"))
    )
    (net (code "233") (name "unconnected-(U1-IO_L23N_T3_FWE_B_15-PadJ18)") (class "Default")
      (node (ref "U1") (pin "J18") (pinfunction "IO_L23N_T3_FWE_B_15_J18") (pintype "passive"))
    )
    (net (code "234") (name "unconnected-(U1-IO_L23P_T3_34-PadR7)") (class "Default")
      (node (ref "U1") (pin "R7") (pinfunction "IO_L23P_T3_34_R7") (pintype "passive"))
    )
    (net (code "235") (name "unconnected-(U1-IO_L23P_T3_35-PadK2)") (class "Default")
      (node (ref "U1") (pin "K2") (pinfunction "IO_L23P_T3_35_K2") (pintype "passive"))
    )
    (net (code "236") (name "unconnected-(U1-IO_L23P_T3_A03_D19_14-PadT13)") (class "Default")
      (node (ref "U1") (pin "T13") (pinfunction "IO_L23P_T3_A03_D19_14_T13") (pintype "passive"))
    )
    (net (code "237") (name "unconnected-(U1-IO_L23P_T3_FOE_B_15-PadJ17)") (class "Default")
      (node (ref "U1") (pin "J17") (pinfunction "IO_L23P_T3_FOE_B_15_J17") (pintype "passive"))
    )
    (net (code "238") (name "unconnected-(U1-IO_L24N_T3_34-PadT8)") (class "Default")
      (node (ref "U1") (pin "T8") (pinfunction "IO_L24N_T3_34_T8") (pintype "passive"))
    )
    (net (code "239") (name "unconnected-(U1-IO_L24N_T3_35-PadH5)") (class "Default")
      (node (ref "U1") (pin "H5") (pinfunction "IO_L24N_T3_35_H5") (pintype "passive"))
    )
    (net (code "240") (name "unconnected-(U1-IO_L24N_T3_A00_D16_14-PadT10)") (class "Default")
      (node (ref "U1") (pin "T10") (pinfunction "IO_L24N_T3_A00_D16_14_T10") (pintype "passive"))
    )
    (net (code "241") (name "unconnected-(U1-IO_L24N_T3_RS0_15-PadJ15)") (class "Default")
      (node (ref "U1") (pin "J15") (pinfunction "IO_L24N_T3_RS0_15_J15") (pintype "passive"))
    )
    (net (code "242") (name "unconnected-(U1-IO_L24P_T3_34-PadR8)") (class "Default")
      (node (ref "U1") (pin "R8") (pinfunction "IO_L24P_T3_34_R8") (pintype "passive"))
    )
    (net (code "243") (name "unconnected-(U1-IO_L24P_T3_35-PadH6)") (class "Default")
      (node (ref "U1") (pin "H6") (pinfunction "IO_L24P_T3_35_H6") (pintype "passive"))
    )
    (net (code "244") (name "unconnected-(U1-IO_L24P_T3_A01_D17_14-PadT9)") (class "Default")
      (node (ref "U1") (pin "T9") (pinfunction "IO_L24P_T3_A01_D17_14_T9") (pintype "passive"))
    )
    (net (code "245") (name "unconnected-(U1-IO_L24P_T3_RS1_15-PadK15)") (class "Default")
      (node (ref "U1") (pin "K15") (pinfunction "IO_L24P_T3_RS1_15_K15") (pintype "passive"))
    )
    (net (code "246") (name "unconnected-(U1-VREFN_0-PadJ9)") (class "Default")
      (node (ref "U1") (pin "J9") (pinfunction "VREFN_0_J9") (pintype "passive"))
    )
    (net (code "247") (name "unconnected-(U1-VREFP_0-PadK10)") (class "Default")
      (node (ref "U1") (pin "K10") (pinfunction "VREFP_0_K10") (pintype "passive"))
    )
  )
)
